# drivers.net
KiCad netlist of a schematic drawn in Altium Designer
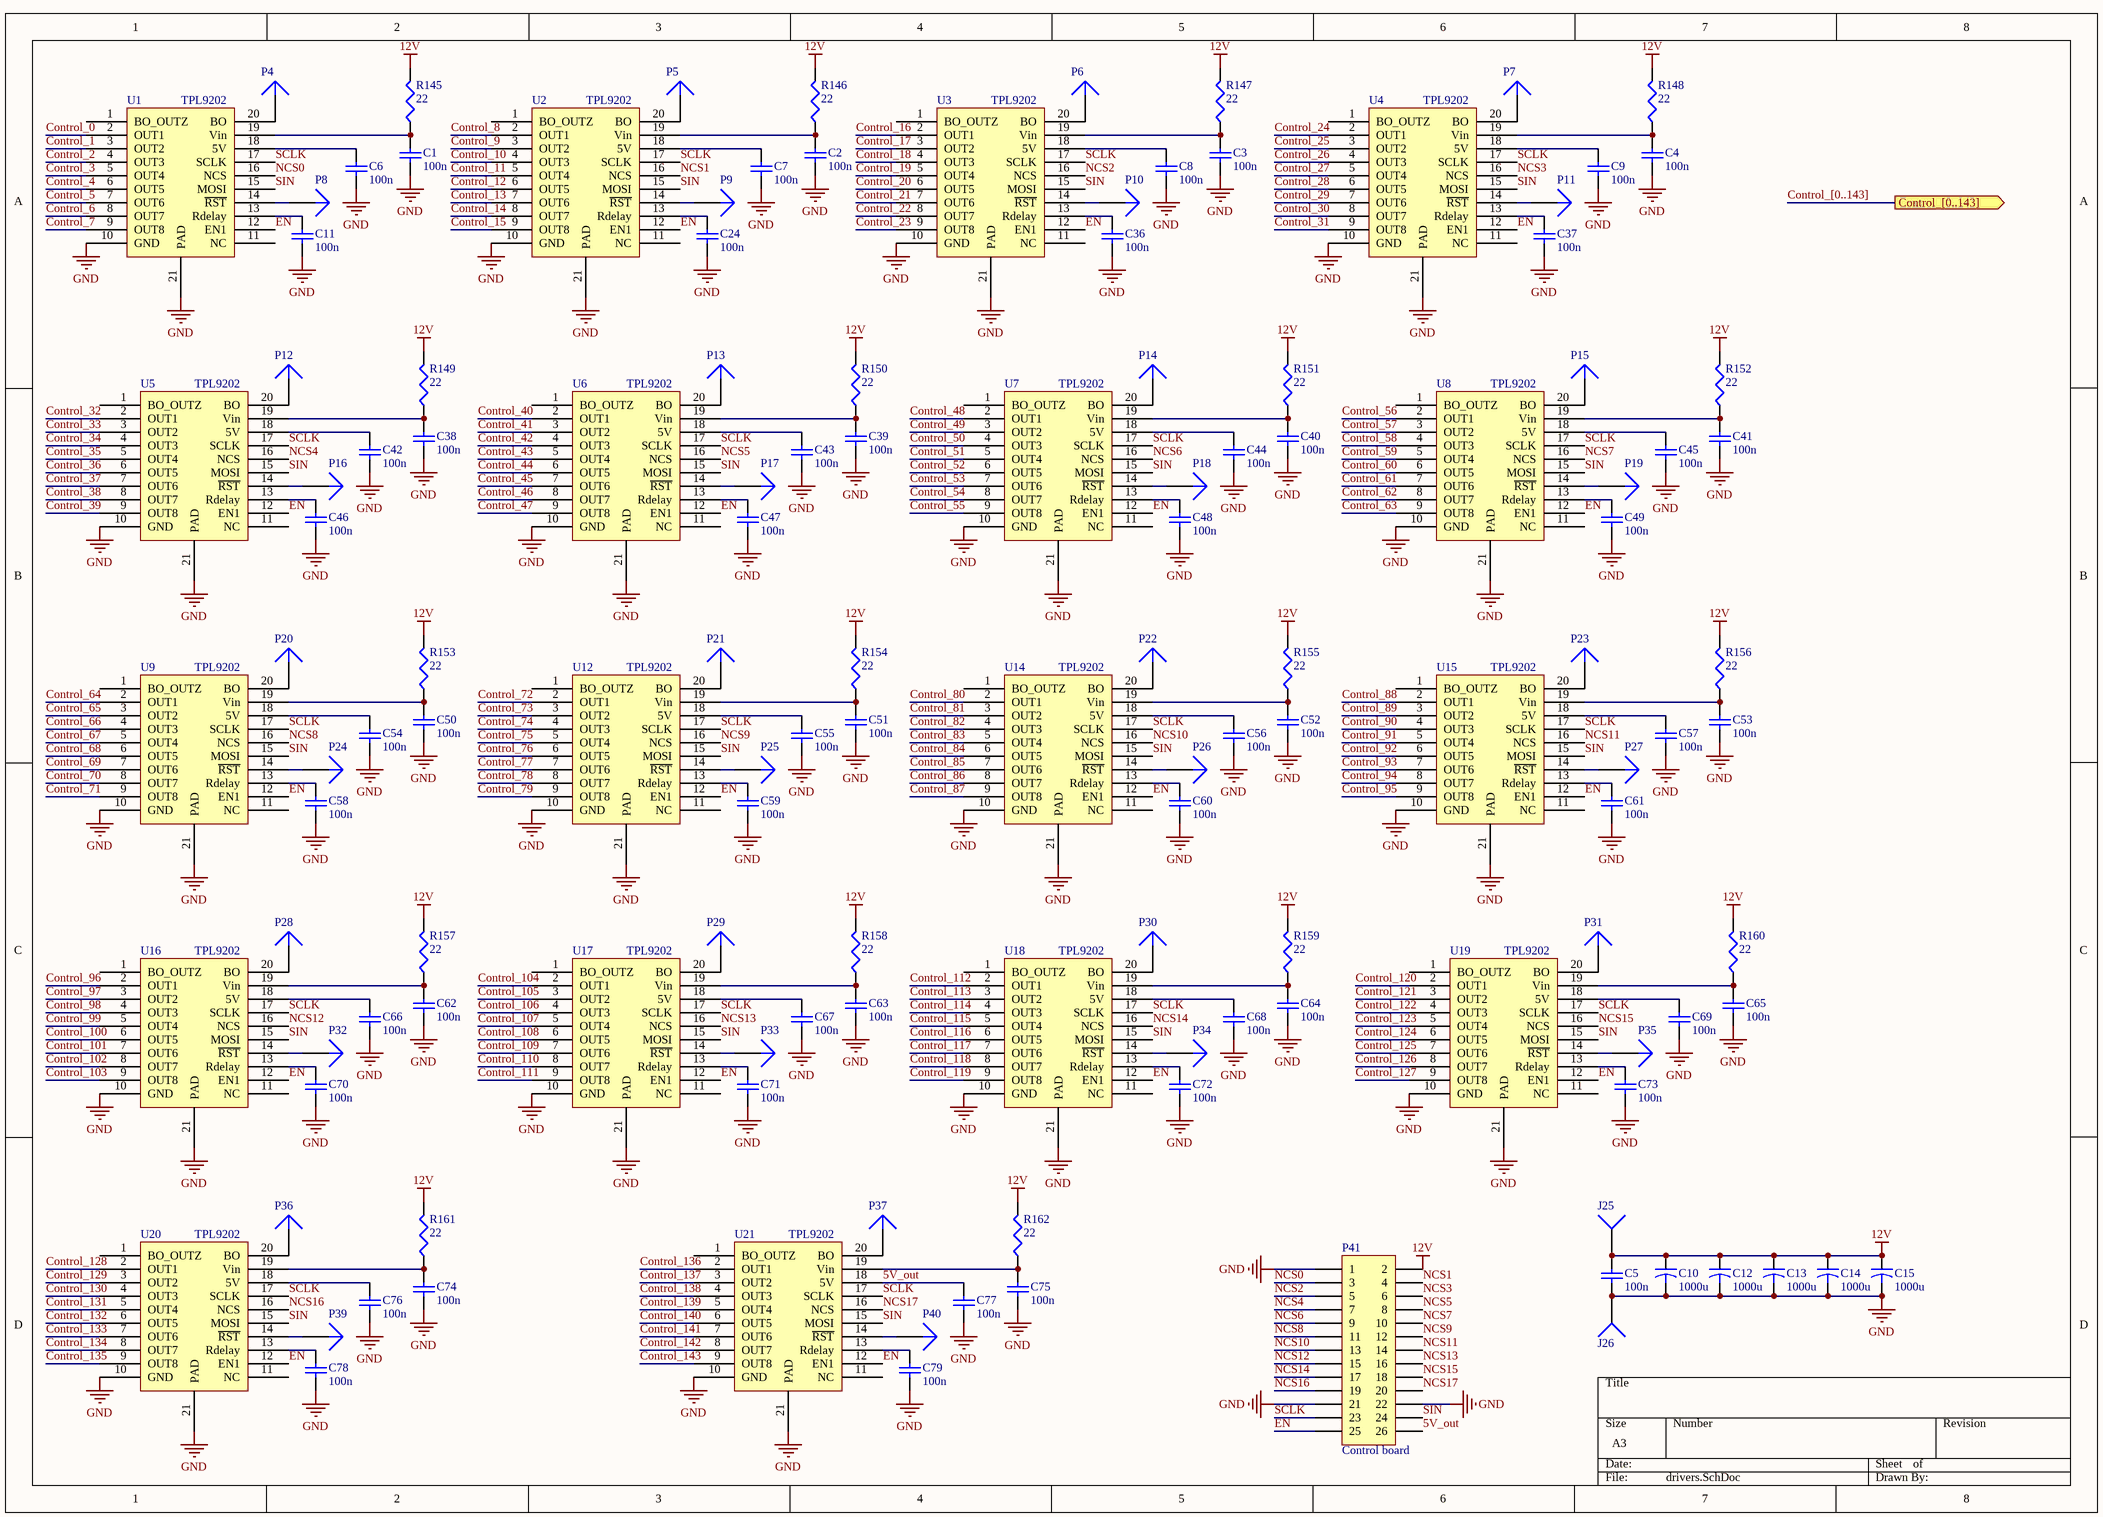
[diagram p0: drivers.SchDoc]

(export (version "E")
  (design (tool "Eeschema 10.0.6"))
  (components
    (comp (ref "C1")
      (value "100n")
      (footprint "1608[0603]")
      (description "Capacitor (Semiconductor SIM Model)")
      (fields (field (name "Comment") "Cap Semi") (field (name "PUBLISHER") "Altium Limited"))
      (libsource (lib "Miscellaneous Devices") (part "Cap Semi"))
    )
    (comp (ref "C2")
      (value "100n")
      (footprint "1608[0603]")
      (description "Capacitor (Semiconductor SIM Model)")
      (fields (field (name "Comment") "Cap Semi") (field (name "PUBLISHER") "Altium Limited"))
      (libsource (lib "Miscellaneous Devices") (part "Cap Semi"))
    )
    (comp (ref "C3")
      (value "100n")
      (footprint "1608[0603]")
      (description "Capacitor (Semiconductor SIM Model)")
      (fields (field (name "Comment") "Cap Semi") (field (name "PUBLISHER") "Altium Limited"))
      (libsource (lib "Miscellaneous Devices") (part "Cap Semi"))
    )
    (comp (ref "C4")
      (value "100n")
      (footprint "1608[0603]")
      (description "Capacitor (Semiconductor SIM Model)")
      (fields (field (name "Comment") "Cap Semi") (field (name "PUBLISHER") "Altium Limited"))
      (libsource (lib "Miscellaneous Devices") (part "Cap Semi"))
    )
    (comp (ref "C5")
      (value "100n")
      (footprint "1608[0603]")
      (description "Capacitor (Semiconductor SIM Model)")
      (fields (field (name "Comment") "Cap Semi") (field (name "PUBLISHER") "Altium Limited"))
      (libsource (lib "Miscellaneous Devices") (part "Cap Semi"))
    )
    (comp (ref "C6")
      (value "100n")
      (footprint "1608[0603]")
      (description "Capacitor (Semiconductor SIM Model)")
      (fields (field (name "Comment") "Cap Semi") (field (name "PUBLISHER") "Altium Limited"))
      (libsource (lib "Miscellaneous Devices") (part "Cap Semi"))
    )
    (comp (ref "C7")
      (value "100n")
      (footprint "1608[0603]")
      (description "Capacitor (Semiconductor SIM Model)")
      (fields (field (name "Comment") "Cap Semi") (field (name "PUBLISHER") "Altium Limited"))
      (libsource (lib "Miscellaneous Devices") (part "Cap Semi"))
    )
    (comp (ref "C8")
      (value "100n")
      (footprint "1608[0603]")
      (description "Capacitor (Semiconductor SIM Model)")
      (fields (field (name "Comment") "Cap Semi") (field (name "PUBLISHER") "Altium Limited"))
      (libsource (lib "Miscellaneous Devices") (part "Cap Semi"))
    )
    (comp (ref "C9")
      (value "100n")
      (footprint "1608[0603]")
      (description "Capacitor (Semiconductor SIM Model)")
      (fields (field (name "Comment") "Cap Semi") (field (name "PUBLISHER") "Altium Limited"))
      (libsource (lib "Miscellaneous Devices") (part "Cap Semi"))
    )
    (comp (ref "C10")
      (value "1000u")
      (footprint "Cap_10x16mm")
      (description "Capacitor")
      (fields (field (name "Comment") "Cap2") (field (name "PUBLISHER") "Altium Limited"))
      (libsource (lib "Miscellaneous Devices") (part "Cap2"))
    )
    (comp (ref "C11")
      (value "100n")
      (footprint "1608[0603]")
      (description "Capacitor (Semiconductor SIM Model)")
      (fields (field (name "Comment") "Cap Semi") (field (name "PUBLISHER") "Altium Limited"))
      (libsource (lib "Miscellaneous Devices") (part "Cap Semi"))
    )
    (comp (ref "C12")
      (value "1000u")
      (footprint "Cap_10x16mm")
      (description "Capacitor")
      (fields (field (name "Comment") "Cap2") (field (name "PUBLISHER") "Altium Limited"))
      (libsource (lib "Miscellaneous Devices") (part "Cap2"))
    )
    (comp (ref "C13")
      (value "1000u")
      (footprint "Cap_10x16mm")
      (description "Capacitor")
      (fields (field (name "Comment") "Cap2") (field (name "PUBLISHER") "Altium Limited"))
      (libsource (lib "Miscellaneous Devices") (part "Cap2"))
    )
    (comp (ref "C14")
      (value "1000u")
      (footprint "Cap_10x16mm")
      (description "Capacitor")
      (fields (field (name "Comment") "Cap2") (field (name "PUBLISHER") "Altium Limited"))
      (libsource (lib "Miscellaneous Devices") (part "Cap2"))
    )
    (comp (ref "C15")
      (value "1000u")
      (footprint "Cap_10x16mm")
      (description "Capacitor")
      (fields (field (name "Comment") "Cap2") (field (name "PUBLISHER") "Altium Limited"))
      (libsource (lib "Miscellaneous Devices") (part "Cap2"))
    )
    (comp (ref "C24")
      (value "100n")
      (footprint "1608[0603]")
      (description "Capacitor (Semiconductor SIM Model)")
      (fields (field (name "Comment") "Cap Semi") (field (name "PUBLISHER") "Altium Limited"))
      (libsource (lib "Miscellaneous Devices") (part "Cap Semi"))
    )
    (comp (ref "C36")
      (value "100n")
      (footprint "1608[0603]")
      (description "Capacitor (Semiconductor SIM Model)")
      (fields (field (name "Comment") "Cap Semi") (field (name "PUBLISHER") "Altium Limited"))
      (libsource (lib "Miscellaneous Devices") (part "Cap Semi"))
    )
    (comp (ref "C37")
      (value "100n")
      (footprint "1608[0603]")
      (description "Capacitor (Semiconductor SIM Model)")
      (fields (field (name "Comment") "Cap Semi") (field (name "PUBLISHER") "Altium Limited"))
      (libsource (lib "Miscellaneous Devices") (part "Cap Semi"))
    )
    (comp (ref "C38")
      (value "100n")
      (footprint "1608[0603]")
      (description "Capacitor (Semiconductor SIM Model)")
      (fields (field (name "Comment") "Cap Semi") (field (name "PUBLISHER") "Altium Limited"))
      (libsource (lib "Miscellaneous Devices") (part "Cap Semi"))
    )
    (comp (ref "C39")
      (value "100n")
      (footprint "1608[0603]")
      (description "Capacitor (Semiconductor SIM Model)")
      (fields (field (name "Comment") "Cap Semi") (field (name "PUBLISHER") "Altium Limited"))
      (libsource (lib "Miscellaneous Devices") (part "Cap Semi"))
    )
    (comp (ref "C40")
      (value "100n")
      (footprint "1608[0603]")
      (description "Capacitor (Semiconductor SIM Model)")
      (fields (field (name "Comment") "Cap Semi") (field (name "PUBLISHER") "Altium Limited"))
      (libsource (lib "Miscellaneous Devices") (part "Cap Semi"))
    )
    (comp (ref "C41")
      (value "100n")
      (footprint "1608[0603]")
      (description "Capacitor (Semiconductor SIM Model)")
      (fields (field (name "Comment") "Cap Semi") (field (name "PUBLISHER") "Altium Limited"))
      (libsource (lib "Miscellaneous Devices") (part "Cap Semi"))
    )
    (comp (ref "C42")
      (value "100n")
      (footprint "1608[0603]")
      (description "Capacitor (Semiconductor SIM Model)")
      (fields (field (name "Comment") "Cap Semi") (field (name "PUBLISHER") "Altium Limited"))
      (libsource (lib "Miscellaneous Devices") (part "Cap Semi"))
    )
    (comp (ref "C43")
      (value "100n")
      (footprint "1608[0603]")
      (description "Capacitor (Semiconductor SIM Model)")
      (fields (field (name "Comment") "Cap Semi") (field (name "PUBLISHER") "Altium Limited"))
      (libsource (lib "Miscellaneous Devices") (part "Cap Semi"))
    )
    (comp (ref "C44")
      (value "100n")
      (footprint "1608[0603]")
      (description "Capacitor (Semiconductor SIM Model)")
      (fields (field (name "Comment") "Cap Semi") (field (name "PUBLISHER") "Altium Limited"))
      (libsource (lib "Miscellaneous Devices") (part "Cap Semi"))
    )
    (comp (ref "C45")
      (value "100n")
      (footprint "1608[0603]")
      (description "Capacitor (Semiconductor SIM Model)")
      (fields (field (name "Comment") "Cap Semi") (field (name "PUBLISHER") "Altium Limited"))
      (libsource (lib "Miscellaneous Devices") (part "Cap Semi"))
    )
    (comp (ref "C46")
      (value "100n")
      (footprint "1608[0603]")
      (description "Capacitor (Semiconductor SIM Model)")
      (fields (field (name "Comment") "Cap Semi") (field (name "PUBLISHER") "Altium Limited"))
      (libsource (lib "Miscellaneous Devices") (part "Cap Semi"))
    )
    (comp (ref "C47")
      (value "100n")
      (footprint "1608[0603]")
      (description "Capacitor (Semiconductor SIM Model)")
      (fields (field (name "Comment") "Cap Semi") (field (name "PUBLISHER") "Altium Limited"))
      (libsource (lib "Miscellaneous Devices") (part "Cap Semi"))
    )
    (comp (ref "C48")
      (value "100n")
      (footprint "1608[0603]")
      (description "Capacitor (Semiconductor SIM Model)")
      (fields (field (name "Comment") "Cap Semi") (field (name "PUBLISHER") "Altium Limited"))
      (libsource (lib "Miscellaneous Devices") (part "Cap Semi"))
    )
    (comp (ref "C49")
      (value "100n")
      (footprint "1608[0603]")
      (description "Capacitor (Semiconductor SIM Model)")
      (fields (field (name "Comment") "Cap Semi") (field (name "PUBLISHER") "Altium Limited"))
      (libsource (lib "Miscellaneous Devices") (part "Cap Semi"))
    )
    (comp (ref "C50")
      (value "100n")
      (footprint "1608[0603]")
      (description "Capacitor (Semiconductor SIM Model)")
      (fields (field (name "Comment") "Cap Semi") (field (name "PUBLISHER") "Altium Limited"))
      (libsource (lib "Miscellaneous Devices") (part "Cap Semi"))
    )
    (comp (ref "C51")
      (value "100n")
      (footprint "1608[0603]")
      (description "Capacitor (Semiconductor SIM Model)")
      (fields (field (name "Comment") "Cap Semi") (field (name "PUBLISHER") "Altium Limited"))
      (libsource (lib "Miscellaneous Devices") (part "Cap Semi"))
    )
    (comp (ref "C52")
      (value "100n")
      (footprint "1608[0603]")
      (description "Capacitor (Semiconductor SIM Model)")
      (fields (field (name "Comment") "Cap Semi") (field (name "PUBLISHER") "Altium Limited"))
      (libsource (lib "Miscellaneous Devices") (part "Cap Semi"))
    )
    (comp (ref "C53")
      (value "100n")
      (footprint "1608[0603]")
      (description "Capacitor (Semiconductor SIM Model)")
      (fields (field (name "Comment") "Cap Semi") (field (name "PUBLISHER") "Altium Limited"))
      (libsource (lib "Miscellaneous Devices") (part "Cap Semi"))
    )
    (comp (ref "C54")
      (value "100n")
      (footprint "1608[0603]")
      (description "Capacitor (Semiconductor SIM Model)")
      (fields (field (name "Comment") "Cap Semi") (field (name "PUBLISHER") "Altium Limited"))
      (libsource (lib "Miscellaneous Devices") (part "Cap Semi"))
    )
    (comp (ref "C55")
      (value "100n")
      (footprint "1608[0603]")
      (description "Capacitor (Semiconductor SIM Model)")
      (fields (field (name "Comment") "Cap Semi") (field (name "PUBLISHER") "Altium Limited"))
      (libsource (lib "Miscellaneous Devices") (part "Cap Semi"))
    )
    (comp (ref "C56")
      (value "100n")
      (footprint "1608[0603]")
      (description "Capacitor (Semiconductor SIM Model)")
      (fields (field (name "Comment") "Cap Semi") (field (name "PUBLISHER") "Altium Limited"))
      (libsource (lib "Miscellaneous Devices") (part "Cap Semi"))
    )
    (comp (ref "C57")
      (value "100n")
      (footprint "1608[0603]")
      (description "Capacitor (Semiconductor SIM Model)")
      (fields (field (name "Comment") "Cap Semi") (field (name "PUBLISHER") "Altium Limited"))
      (libsource (lib "Miscellaneous Devices") (part "Cap Semi"))
    )
    (comp (ref "C58")
      (value "100n")
      (footprint "1608[0603]")
      (description "Capacitor (Semiconductor SIM Model)")
      (fields (field (name "Comment") "Cap Semi") (field (name "PUBLISHER") "Altium Limited"))
      (libsource (lib "Miscellaneous Devices") (part "Cap Semi"))
    )
    (comp (ref "C59")
      (value "100n")
      (footprint "1608[0603]")
      (description "Capacitor (Semiconductor SIM Model)")
      (fields (field (name "Comment") "Cap Semi") (field (name "PUBLISHER") "Altium Limited"))
      (libsource (lib "Miscellaneous Devices") (part "Cap Semi"))
    )
    (comp (ref "C60")
      (value "100n")
      (footprint "1608[0603]")
      (description "Capacitor (Semiconductor SIM Model)")
      (fields (field (name "Comment") "Cap Semi") (field (name "PUBLISHER") "Altium Limited"))
      (libsource (lib "Miscellaneous Devices") (part "Cap Semi"))
    )
    (comp (ref "C61")
      (value "100n")
      (footprint "1608[0603]")
      (description "Capacitor (Semiconductor SIM Model)")
      (fields (field (name "Comment") "Cap Semi") (field (name "PUBLISHER") "Altium Limited"))
      (libsource (lib "Miscellaneous Devices") (part "Cap Semi"))
    )
    (comp (ref "C62")
      (value "100n")
      (footprint "1608[0603]")
      (description "Capacitor (Semiconductor SIM Model)")
      (fields (field (name "Comment") "Cap Semi") (field (name "PUBLISHER") "Altium Limited"))
      (libsource (lib "Miscellaneous Devices") (part "Cap Semi"))
    )
    (comp (ref "C63")
      (value "100n")
      (footprint "1608[0603]")
      (description "Capacitor (Semiconductor SIM Model)")
      (fields (field (name "Comment") "Cap Semi") (field (name "PUBLISHER") "Altium Limited"))
      (libsource (lib "Miscellaneous Devices") (part "Cap Semi"))
    )
    (comp (ref "C64")
      (value "100n")
      (footprint "1608[0603]")
      (description "Capacitor (Semiconductor SIM Model)")
      (fields (field (name "Comment") "Cap Semi") (field (name "PUBLISHER") "Altium Limited"))
      (libsource (lib "Miscellaneous Devices") (part "Cap Semi"))
    )
    (comp (ref "C65")
      (value "100n")
      (footprint "1608[0603]")
      (description "Capacitor (Semiconductor SIM Model)")
      (fields (field (name "Comment") "Cap Semi") (field (name "PUBLISHER") "Altium Limited"))
      (libsource (lib "Miscellaneous Devices") (part "Cap Semi"))
    )
    (comp (ref "C66")
      (value "100n")
      (footprint "1608[0603]")
      (description "Capacitor (Semiconductor SIM Model)")
      (fields (field (name "Comment") "Cap Semi") (field (name "PUBLISHER") "Altium Limited"))
      (libsource (lib "Miscellaneous Devices") (part "Cap Semi"))
    )
    (comp (ref "C67")
      (value "100n")
      (footprint "1608[0603]")
      (description "Capacitor (Semiconductor SIM Model)")
      (fields (field (name "Comment") "Cap Semi") (field (name "PUBLISHER") "Altium Limited"))
      (libsource (lib "Miscellaneous Devices") (part "Cap Semi"))
    )
    (comp (ref "C68")
      (value "100n")
      (footprint "1608[0603]")
      (description "Capacitor (Semiconductor SIM Model)")
      (fields (field (name "Comment") "Cap Semi") (field (name "PUBLISHER") "Altium Limited"))
      (libsource (lib "Miscellaneous Devices") (part "Cap Semi"))
    )
    (comp (ref "C69")
      (value "100n")
      (footprint "1608[0603]")
      (description "Capacitor (Semiconductor SIM Model)")
      (fields (field (name "Comment") "Cap Semi") (field (name "PUBLISHER") "Altium Limited"))
      (libsource (lib "Miscellaneous Devices") (part "Cap Semi"))
    )
    (comp (ref "C70")
      (value "100n")
      (footprint "1608[0603]")
      (description "Capacitor (Semiconductor SIM Model)")
      (fields (field (name "Comment") "Cap Semi") (field (name "PUBLISHER") "Altium Limited"))
      (libsource (lib "Miscellaneous Devices") (part "Cap Semi"))
    )
    (comp (ref "C71")
      (value "100n")
      (footprint "1608[0603]")
      (description "Capacitor (Semiconductor SIM Model)")
      (fields (field (name "Comment") "Cap Semi") (field (name "PUBLISHER") "Altium Limited"))
      (libsource (lib "Miscellaneous Devices") (part "Cap Semi"))
    )
    (comp (ref "C72")
      (value "100n")
      (footprint "1608[0603]")
      (description "Capacitor (Semiconductor SIM Model)")
      (fields (field (name "Comment") "Cap Semi") (field (name "PUBLISHER") "Altium Limited"))
      (libsource (lib "Miscellaneous Devices") (part "Cap Semi"))
    )
    (comp (ref "C73")
      (value "100n")
      (footprint "1608[0603]")
      (description "Capacitor (Semiconductor SIM Model)")
      (fields (field (name "Comment") "Cap Semi") (field (name "PUBLISHER") "Altium Limited"))
      (libsource (lib "Miscellaneous Devices") (part "Cap Semi"))
    )
    (comp (ref "C74")
      (value "100n")
      (footprint "1608[0603]")
      (description "Capacitor (Semiconductor SIM Model)")
      (fields (field (name "Comment") "Cap Semi") (field (name "PUBLISHER") "Altium Limited"))
      (libsource (lib "Miscellaneous Devices") (part "Cap Semi"))
    )
    (comp (ref "C75")
      (value "100n")
      (footprint "1608[0603]")
      (description "Capacitor (Semiconductor SIM Model)")
      (fields (field (name "Comment") "Cap Semi") (field (name "PUBLISHER") "Altium Limited"))
      (libsource (lib "Miscellaneous Devices") (part "Cap Semi"))
    )
    (comp (ref "C76")
      (value "100n")
      (footprint "1608[0603]")
      (description "Capacitor (Semiconductor SIM Model)")
      (fields (field (name "Comment") "Cap Semi") (field (name "PUBLISHER") "Altium Limited"))
      (libsource (lib "Miscellaneous Devices") (part "Cap Semi"))
    )
    (comp (ref "C77")
      (value "100n")
      (footprint "1608[0603]")
      (description "Capacitor (Semiconductor SIM Model)")
      (fields (field (name "Comment") "Cap Semi") (field (name "PUBLISHER") "Altium Limited"))
      (libsource (lib "Miscellaneous Devices") (part "Cap Semi"))
    )
    (comp (ref "C78")
      (value "100n")
      (footprint "1608[0603]")
      (description "Capacitor (Semiconductor SIM Model)")
      (fields (field (name "Comment") "Cap Semi") (field (name "PUBLISHER") "Altium Limited"))
      (libsource (lib "Miscellaneous Devices") (part "Cap Semi"))
    )
    (comp (ref "C79")
      (value "100n")
      (footprint "1608[0603]")
      (description "Capacitor (Semiconductor SIM Model)")
      (fields (field (name "Comment") "Cap Semi") (field (name "PUBLISHER") "Altium Limited"))
      (libsource (lib "Miscellaneous Devices") (part "Cap Semi"))
    )
    (comp (ref "J25")
      (value "Audio")
      (footprint "Conn_1_2x4")
      (description "Socket")
      (fields (field (name "PUBLISHER") "Altium Limited"))
      (libsource (lib "Miscellaneous Connectors") (part "Socket"))
    )
    (comp (ref "J26")
      (value "Audio")
      (footprint "Conn_1_2x4")
      (description "Socket")
      (fields (field (name "PUBLISHER") "Altium Limited"))
      (libsource (lib "Miscellaneous Connectors") (part "Socket"))
    )
    (comp (ref "P4")
      (value "Plug")
      (footprint "PIN1")
      (fields (field (name "PUBLISHER") "Altium Limited"))
      (libsource (lib "Miscellaneous Connectors") (part "Plug"))
    )
    (comp (ref "P5")
      (value "Plug")
      (footprint "PIN1")
      (fields (field (name "PUBLISHER") "Altium Limited"))
      (libsource (lib "Miscellaneous Connectors") (part "Plug"))
    )
    (comp (ref "P6")
      (value "Plug")
      (footprint "PIN1")
      (fields (field (name "PUBLISHER") "Altium Limited"))
      (libsource (lib "Miscellaneous Connectors") (part "Plug"))
    )
    (comp (ref "P7")
      (value "Plug")
      (footprint "PIN1")
      (fields (field (name "PUBLISHER") "Altium Limited"))
      (libsource (lib "Miscellaneous Connectors") (part "Plug"))
    )
    (comp (ref "P8")
      (value "Plug")
      (footprint "PIN1")
      (fields (field (name "PUBLISHER") "Altium Limited"))
      (libsource (lib "Miscellaneous Connectors") (part "Plug"))
    )
    (comp (ref "P9")
      (value "Plug")
      (footprint "PIN1")
      (fields (field (name "PUBLISHER") "Altium Limited"))
      (libsource (lib "Miscellaneous Connectors") (part "Plug"))
    )
    (comp (ref "P10")
      (value "Plug")
      (footprint "PIN1")
      (fields (field (name "PUBLISHER") "Altium Limited"))
      (libsource (lib "Miscellaneous Connectors") (part "Plug"))
    )
    (comp (ref "P11")
      (value "Plug")
      (footprint "PIN1")
      (fields (field (name "PUBLISHER") "Altium Limited"))
      (libsource (lib "Miscellaneous Connectors") (part "Plug"))
    )
    (comp (ref "P12")
      (value "Plug")
      (footprint "PIN1")
      (fields (field (name "PUBLISHER") "Altium Limited"))
      (libsource (lib "Miscellaneous Connectors") (part "Plug"))
    )
    (comp (ref "P13")
      (value "Plug")
      (footprint "PIN1")
      (fields (field (name "PUBLISHER") "Altium Limited"))
      (libsource (lib "Miscellaneous Connectors") (part "Plug"))
    )
    (comp (ref "P14")
      (value "Plug")
      (footprint "PIN1")
      (fields (field (name "PUBLISHER") "Altium Limited"))
      (libsource (lib "Miscellaneous Connectors") (part "Plug"))
    )
    (comp (ref "P15")
      (value "Plug")
      (footprint "PIN1")
      (fields (field (name "PUBLISHER") "Altium Limited"))
      (libsource (lib "Miscellaneous Connectors") (part "Plug"))
    )
    (comp (ref "P16")
      (value "Plug")
      (footprint "PIN1")
      (fields (field (name "PUBLISHER") "Altium Limited"))
      (libsource (lib "Miscellaneous Connectors") (part "Plug"))
    )
    (comp (ref "P17")
      (value "Plug")
      (footprint "PIN1")
      (fields (field (name "PUBLISHER") "Altium Limited"))
      (libsource (lib "Miscellaneous Connectors") (part "Plug"))
    )
    (comp (ref "P18")
      (value "Plug")
      (footprint "PIN1")
      (fields (field (name "PUBLISHER") "Altium Limited"))
      (libsource (lib "Miscellaneous Connectors") (part "Plug"))
    )
    (comp (ref "P19")
      (value "Plug")
      (footprint "PIN1")
      (fields (field (name "PUBLISHER") "Altium Limited"))
      (libsource (lib "Miscellaneous Connectors") (part "Plug"))
    )
    (comp (ref "P20")
      (value "Plug")
      (footprint "PIN1")
      (fields (field (name "PUBLISHER") "Altium Limited"))
      (libsource (lib "Miscellaneous Connectors") (part "Plug"))
    )
    (comp (ref "P21")
      (value "Plug")
      (footprint "PIN1")
      (fields (field (name "PUBLISHER") "Altium Limited"))
      (libsource (lib "Miscellaneous Connectors") (part "Plug"))
    )
    (comp (ref "P22")
      (value "Plug")
      (footprint "PIN1")
      (fields (field (name "PUBLISHER") "Altium Limited"))
      (libsource (lib "Miscellaneous Connectors") (part "Plug"))
    )
    (comp (ref "P23")
      (value "Plug")
      (footprint "PIN1")
      (fields (field (name "PUBLISHER") "Altium Limited"))
      (libsource (lib "Miscellaneous Connectors") (part "Plug"))
    )
    (comp (ref "P24")
      (value "Plug")
      (footprint "PIN1")
      (fields (field (name "PUBLISHER") "Altium Limited"))
      (libsource (lib "Miscellaneous Connectors") (part "Plug"))
    )
    (comp (ref "P25")
      (value "Plug")
      (footprint "PIN1")
      (fields (field (name "PUBLISHER") "Altium Limited"))
      (libsource (lib "Miscellaneous Connectors") (part "Plug"))
    )
    (comp (ref "P26")
      (value "Plug")
      (footprint "PIN1")
      (fields (field (name "PUBLISHER") "Altium Limited"))
      (libsource (lib "Miscellaneous Connectors") (part "Plug"))
    )
    (comp (ref "P27")
      (value "Plug")
      (footprint "PIN1")
      (fields (field (name "PUBLISHER") "Altium Limited"))
      (libsource (lib "Miscellaneous Connectors") (part "Plug"))
    )
    (comp (ref "P28")
      (value "Plug")
      (footprint "PIN1")
      (fields (field (name "PUBLISHER") "Altium Limited"))
      (libsource (lib "Miscellaneous Connectors") (part "Plug"))
    )
    (comp (ref "P29")
      (value "Plug")
      (footprint "PIN1")
      (fields (field (name "PUBLISHER") "Altium Limited"))
      (libsource (lib "Miscellaneous Connectors") (part "Plug"))
    )
    (comp (ref "P30")
      (value "Plug")
      (footprint "PIN1")
      (fields (field (name "PUBLISHER") "Altium Limited"))
      (libsource (lib "Miscellaneous Connectors") (part "Plug"))
    )
    (comp (ref "P31")
      (value "Plug")
      (footprint "PIN1")
      (fields (field (name "PUBLISHER") "Altium Limited"))
      (libsource (lib "Miscellaneous Connectors") (part "Plug"))
    )
    (comp (ref "P32")
      (value "Plug")
      (footprint "PIN1")
      (fields (field (name "PUBLISHER") "Altium Limited"))
      (libsource (lib "Miscellaneous Connectors") (part "Plug"))
    )
    (comp (ref "P33")
      (value "Plug")
      (footprint "PIN1")
      (fields (field (name "PUBLISHER") "Altium Limited"))
      (libsource (lib "Miscellaneous Connectors") (part "Plug"))
    )
    (comp (ref "P34")
      (value "Plug")
      (footprint "PIN1")
      (fields (field (name "PUBLISHER") "Altium Limited"))
      (libsource (lib "Miscellaneous Connectors") (part "Plug"))
    )
    (comp (ref "P35")
      (value "Plug")
      (footprint "PIN1")
      (fields (field (name "PUBLISHER") "Altium Limited"))
      (libsource (lib "Miscellaneous Connectors") (part "Plug"))
    )
    (comp (ref "P36")
      (value "Plug")
      (footprint "PIN1")
      (fields (field (name "PUBLISHER") "Altium Limited"))
      (libsource (lib "Miscellaneous Connectors") (part "Plug"))
    )
    (comp (ref "P37")
      (value "Plug")
      (footprint "PIN1")
      (fields (field (name "PUBLISHER") "Altium Limited"))
      (libsource (lib "Miscellaneous Connectors") (part "Plug"))
    )
    (comp (ref "P39")
      (value "Plug")
      (footprint "PIN1")
      (fields (field (name "PUBLISHER") "Altium Limited"))
      (libsource (lib "Miscellaneous Connectors") (part "Plug"))
    )
    (comp (ref "P40")
      (value "Plug")
      (footprint "PIN1")
      (fields (field (name "PUBLISHER") "Altium Limited"))
      (libsource (lib "Miscellaneous Connectors") (part "Plug"))
    )
    (comp (ref "P41")
      (value "Control board")
      (footprint "HDR2X13")
      (description "Header, 13-Pin, Dual row")
      (fields (field (name "PUBLISHER") "Altium Limited"))
      (libsource (lib "Miscellaneous Connectors") (part "Header 13X2"))
    )
    (comp (ref "R145")
      (value "22")
      (footprint "C2512")
      (description "Resistor")
      (fields (field (name "Comment") "Res3") (field (name "PUBLISHER") "Altium Limited"))
      (libsource (lib "Miscellaneous Devices") (part "Res3"))
    )
    (comp (ref "R146")
      (value "22")
      (footprint "C2512")
      (description "Resistor")
      (fields (field (name "Comment") "Res3") (field (name "PUBLISHER") "Altium Limited"))
      (libsource (lib "Miscellaneous Devices") (part "Res3"))
    )
    (comp (ref "R147")
      (value "22")
      (footprint "C2512")
      (description "Resistor")
      (fields (field (name "Comment") "Res3") (field (name "PUBLISHER") "Altium Limited"))
      (libsource (lib "Miscellaneous Devices") (part "Res3"))
    )
    (comp (ref "R148")
      (value "22")
      (footprint "C2512")
      (description "Resistor")
      (fields (field (name "Comment") "Res3") (field (name "PUBLISHER") "Altium Limited"))
      (libsource (lib "Miscellaneous Devices") (part "Res3"))
    )
    (comp (ref "R149")
      (value "22")
      (footprint "C2512")
      (description "Resistor")
      (fields (field (name "Comment") "Res3") (field (name "PUBLISHER") "Altium Limited"))
      (libsource (lib "Miscellaneous Devices") (part "Res3"))
    )
    (comp (ref "R150")
      (value "22")
      (footprint "C2512")
      (description "Resistor")
      (fields (field (name "Comment") "Res3") (field (name "PUBLISHER") "Altium Limited"))
      (libsource (lib "Miscellaneous Devices") (part "Res3"))
    )
    (comp (ref "R151")
      (value "22")
      (footprint "C2512")
      (description "Resistor")
      (fields (field (name "Comment") "Res3") (field (name "PUBLISHER") "Altium Limited"))
      (libsource (lib "Miscellaneous Devices") (part "Res3"))
    )
    (comp (ref "R152")
      (value "22")
      (footprint "C2512")
      (description "Resistor")
      (fields (field (name "Comment") "Res3") (field (name "PUBLISHER") "Altium Limited"))
      (libsource (lib "Miscellaneous Devices") (part "Res3"))
    )
    (comp (ref "R153")
      (value "22")
      (footprint "C2512")
      (description "Resistor")
      (fields (field (name "Comment") "Res3") (field (name "PUBLISHER") "Altium Limited"))
      (libsource (lib "Miscellaneous Devices") (part "Res3"))
    )
    (comp (ref "R154")
      (value "22")
      (footprint "C2512")
      (description "Resistor")
      (fields (field (name "Comment") "Res3") (field (name "PUBLISHER") "Altium Limited"))
      (libsource (lib "Miscellaneous Devices") (part "Res3"))
    )
    (comp (ref "R155")
      (value "22")
      (footprint "C2512")
      (description "Resistor")
      (fields (field (name "Comment") "Res3") (field (name "PUBLISHER") "Altium Limited"))
      (libsource (lib "Miscellaneous Devices") (part "Res3"))
    )
    (comp (ref "R156")
      (value "22")
      (footprint "C2512")
      (description "Resistor")
      (fields (field (name "Comment") "Res3") (field (name "PUBLISHER") "Altium Limited"))
      (libsource (lib "Miscellaneous Devices") (part "Res3"))
    )
    (comp (ref "R157")
      (value "22")
      (footprint "C2512")
      (description "Resistor")
      (fields (field (name "Comment") "Res3") (field (name "PUBLISHER") "Altium Limited"))
      (libsource (lib "Miscellaneous Devices") (part "Res3"))
    )
    (comp (ref "R158")
      (value "22")
      (footprint "C2512")
      (description "Resistor")
      (fields (field (name "Comment") "Res3") (field (name "PUBLISHER") "Altium Limited"))
      (libsource (lib "Miscellaneous Devices") (part "Res3"))
    )
    (comp (ref "R159")
      (value "22")
      (footprint "C2512")
      (description "Resistor")
      (fields (field (name "Comment") "Res3") (field (name "PUBLISHER") "Altium Limited"))
      (libsource (lib "Miscellaneous Devices") (part "Res3"))
    )
    (comp (ref "R160")
      (value "22")
      (footprint "C2512")
      (description "Resistor")
      (fields (field (name "Comment") "Res3") (field (name "PUBLISHER") "Altium Limited"))
      (libsource (lib "Miscellaneous Devices") (part "Res3"))
    )
    (comp (ref "R161")
      (value "22")
      (footprint "C2512")
      (description "Resistor")
      (fields (field (name "Comment") "Res3") (field (name "PUBLISHER") "Altium Limited"))
      (libsource (lib "Miscellaneous Devices") (part "Res3"))
    )
    (comp (ref "R162")
      (value "22")
      (footprint "C2512")
      (description "Resistor")
      (fields (field (name "Comment") "Res3") (field (name "PUBLISHER") "Altium Limited"))
      (libsource (lib "Miscellaneous Devices") (part "Res3"))
    )
    (comp (ref "U1")
      (value "TPL9202")
      (footprint "HSSOP20")
      (description "8-CHANNEL RELAY DRIVER  WITH INTEGRATED 5-V LDO AND BROWN-OUT DETECTION")
      (fields (field (name "PART NUMBER") "809-5425"))
      (libsource (lib "tech-thing") (part "TPL9202"))
    )
    (comp (ref "U2")
      (value "TPL9202")
      (footprint "HSSOP20")
      (description "8-CHANNEL RELAY DRIVER  WITH INTEGRATED 5-V LDO AND BROWN-OUT DETECTION")
      (fields (field (name "PART NUMBER") "809-5425"))
      (libsource (lib "tech-thing") (part "TPL9202"))
    )
    (comp (ref "U3")
      (value "TPL9202")
      (footprint "HSSOP20")
      (description "8-CHANNEL RELAY DRIVER  WITH INTEGRATED 5-V LDO AND BROWN-OUT DETECTION")
      (fields (field (name "PART NUMBER") "809-5425"))
      (libsource (lib "tech-thing") (part "TPL9202"))
    )
    (comp (ref "U4")
      (value "TPL9202")
      (footprint "HSSOP20")
      (description "8-CHANNEL RELAY DRIVER  WITH INTEGRATED 5-V LDO AND BROWN-OUT DETECTION")
      (fields (field (name "PART NUMBER") "809-5425"))
      (libsource (lib "tech-thing") (part "TPL9202"))
    )
    (comp (ref "U5")
      (value "TPL9202")
      (footprint "HSSOP20")
      (description "8-CHANNEL RELAY DRIVER  WITH INTEGRATED 5-V LDO AND BROWN-OUT DETECTION")
      (fields (field (name "PART NUMBER") "809-5425"))
      (libsource (lib "tech-thing") (part "TPL9202"))
    )
    (comp (ref "U6")
      (value "TPL9202")
      (footprint "HSSOP20")
      (description "8-CHANNEL RELAY DRIVER  WITH INTEGRATED 5-V LDO AND BROWN-OUT DETECTION")
      (fields (field (name "PART NUMBER") "809-5425"))
      (libsource (lib "tech-thing") (part "TPL9202"))
    )
    (comp (ref "U7")
      (value "TPL9202")
      (footprint "HSSOP20")
      (description "8-CHANNEL RELAY DRIVER  WITH INTEGRATED 5-V LDO AND BROWN-OUT DETECTION")
      (fields (field (name "PART NUMBER") "809-5425"))
      (libsource (lib "tech-thing") (part "TPL9202"))
    )
    (comp (ref "U8")
      (value "TPL9202")
      (footprint "HSSOP20")
      (description "8-CHANNEL RELAY DRIVER  WITH INTEGRATED 5-V LDO AND BROWN-OUT DETECTION")
      (fields (field (name "PART NUMBER") "809-5425"))
      (libsource (lib "tech-thing") (part "TPL9202"))
    )
    (comp (ref "U9")
      (value "TPL9202")
      (footprint "HSSOP20")
      (description "8-CHANNEL RELAY DRIVER  WITH INTEGRATED 5-V LDO AND BROWN-OUT DETECTION")
      (fields (field (name "PART NUMBER") "809-5425"))
      (libsource (lib "tech-thing") (part "TPL9202"))
    )
    (comp (ref "U12")
      (value "TPL9202")
      (footprint "HSSOP20")
      (description "8-CHANNEL RELAY DRIVER  WITH INTEGRATED 5-V LDO AND BROWN-OUT DETECTION")
      (fields (field (name "PART NUMBER") "809-5425"))
      (libsource (lib "tech-thing") (part "TPL9202"))
    )
    (comp (ref "U14")
      (value "TPL9202")
      (footprint "HSSOP20")
      (description "8-CHANNEL RELAY DRIVER  WITH INTEGRATED 5-V LDO AND BROWN-OUT DETECTION")
      (fields (field (name "PART NUMBER") "809-5425"))
      (libsource (lib "tech-thing") (part "TPL9202"))
    )
    (comp (ref "U15")
      (value "TPL9202")
      (footprint "HSSOP20")
      (description "8-CHANNEL RELAY DRIVER  WITH INTEGRATED 5-V LDO AND BROWN-OUT DETECTION")
      (fields (field (name "PART NUMBER") "809-5425"))
      (libsource (lib "tech-thing") (part "TPL9202"))
    )
    (comp (ref "U16")
      (value "TPL9202")
      (footprint "HSSOP20")
      (description "8-CHANNEL RELAY DRIVER  WITH INTEGRATED 5-V LDO AND BROWN-OUT DETECTION")
      (fields (field (name "PART NUMBER") "809-5425"))
      (libsource (lib "tech-thing") (part "TPL9202"))
    )
    (comp (ref "U17")
      (value "TPL9202")
      (footprint "HSSOP20")
      (description "8-CHANNEL RELAY DRIVER  WITH INTEGRATED 5-V LDO AND BROWN-OUT DETECTION")
      (fields (field (name "PART NUMBER") "809-5425"))
      (libsource (lib "tech-thing") (part "TPL9202"))
    )
    (comp (ref "U18")
      (value "TPL9202")
      (footprint "HSSOP20")
      (description "8-CHANNEL RELAY DRIVER  WITH INTEGRATED 5-V LDO AND BROWN-OUT DETECTION")
      (fields (field (name "PART NUMBER") "809-5425"))
      (libsource (lib "tech-thing") (part "TPL9202"))
    )
    (comp (ref "U19")
      (value "TPL9202")
      (footprint "HSSOP20")
      (description "8-CHANNEL RELAY DRIVER  WITH INTEGRATED 5-V LDO AND BROWN-OUT DETECTION")
      (fields (field (name "PART NUMBER") "809-5425"))
      (libsource (lib "tech-thing") (part "TPL9202"))
    )
    (comp (ref "U20")
      (value "TPL9202")
      (footprint "HSSOP20")
      (description "8-CHANNEL RELAY DRIVER  WITH INTEGRATED 5-V LDO AND BROWN-OUT DETECTION")
      (fields (field (name "PART NUMBER") "809-5425"))
      (libsource (lib "tech-thing") (part "TPL9202"))
    )
    (comp (ref "U21")
      (value "TPL9202")
      (footprint "HSSOP20")
      (description "8-CHANNEL RELAY DRIVER  WITH INTEGRATED 5-V LDO AND BROWN-OUT DETECTION")
      (fields (field (name "PART NUMBER") "809-5425"))
      (libsource (lib "tech-thing") (part "TPL9202"))
    )
  )
  (nets
    (net (code "1") (name "/5V_out") (class "Default")
      (node (ref "C77") (pin "2") (pinfunction "2_2") (pintype "passive"))
      (node (ref "P41") (pin "26") (pinfunction "26_26") (pintype "passive"))
      (node (ref "U21") (pin "18") (pinfunction "5V_18") (pintype "passive"))
    )
    (net (code "2") (name "/Control_0") (class "Default")
      (node (ref "U1") (pin "2") (pinfunction "OUT1_2") (pintype "passive"))
    )
    (net (code "3") (name "/Control_1") (class "Default")
      (node (ref "U1") (pin "3") (pinfunction "OUT2_3") (pintype "passive"))
    )
    (net (code "4") (name "/Control_2") (class "Default")
      (node (ref "U1") (pin "4") (pinfunction "OUT3_4") (pintype "passive"))
    )
    (net (code "5") (name "/Control_3") (class "Default")
      (node (ref "U1") (pin "5") (pinfunction "OUT4_5") (pintype "passive"))
    )
    (net (code "6") (name "/Control_4") (class "Default")
      (node (ref "U1") (pin "6") (pinfunction "OUT5_6") (pintype "passive"))
    )
    (net (code "7") (name "/Control_5") (class "Default")
      (node (ref "U1") (pin "7") (pinfunction "OUT6_7") (pintype "passive"))
    )
    (net (code "8") (name "/Control_6") (class "Default")
      (node (ref "U1") (pin "8") (pinfunction "OUT7_8") (pintype "passive"))
    )
    (net (code "9") (name "/Control_7") (class "Default")
      (node (ref "U1") (pin "9") (pinfunction "OUT8_9") (pintype "passive"))
    )
    (net (code "10") (name "/Control_8") (class "Default")
      (node (ref "U2") (pin "2") (pinfunction "OUT1_2") (pintype "passive"))
    )
    (net (code "11") (name "/Control_9") (class "Default")
      (node (ref "U2") (pin "3") (pinfunction "OUT2_3") (pintype "passive"))
    )
    (net (code "12") (name "/Control_10") (class "Default")
      (node (ref "U2") (pin "4") (pinfunction "OUT3_4") (pintype "passive"))
    )
    (net (code "13") (name "/Control_11") (class "Default")
      (node (ref "U2") (pin "5") (pinfunction "OUT4_5") (pintype "passive"))
    )
    (net (code "14") (name "/Control_12") (class "Default")
      (node (ref "U2") (pin "6") (pinfunction "OUT5_6") (pintype "passive"))
    )
    (net (code "15") (name "/Control_13") (class "Default")
      (node (ref "U2") (pin "7") (pinfunction "OUT6_7") (pintype "passive"))
    )
    (net (code "16") (name "/Control_14") (class "Default")
      (node (ref "U2") (pin "8") (pinfunction "OUT7_8") (pintype "passive"))
    )
    (net (code "17") (name "/Control_15") (class "Default")
      (node (ref "U2") (pin "9") (pinfunction "OUT8_9") (pintype "passive"))
    )
    (net (code "18") (name "/Control_16") (class "Default")
      (node (ref "U3") (pin "2") (pinfunction "OUT1_2") (pintype "passive"))
    )
    (net (code "19") (name "/Control_17") (class "Default")
      (node (ref "U3") (pin "3") (pinfunction "OUT2_3") (pintype "passive"))
    )
    (net (code "20") (name "/Control_18") (class "Default")
      (node (ref "U3") (pin "4") (pinfunction "OUT3_4") (pintype "passive"))
    )
    (net (code "21") (name "/Control_19") (class "Default")
      (node (ref "U3") (pin "5") (pinfunction "OUT4_5") (pintype "passive"))
    )
    (net (code "22") (name "/Control_20") (class "Default")
      (node (ref "U3") (pin "6") (pinfunction "OUT5_6") (pintype "passive"))
    )
    (net (code "23") (name "/Control_21") (class "Default")
      (node (ref "U3") (pin "7") (pinfunction "OUT6_7") (pintype "passive"))
    )
    (net (code "24") (name "/Control_22") (class "Default")
      (node (ref "U3") (pin "8") (pinfunction "OUT7_8") (pintype "passive"))
    )
    (net (code "25") (name "/Control_23") (class "Default")
      (node (ref "U3") (pin "9") (pinfunction "OUT8_9") (pintype "passive"))
    )
    (net (code "26") (name "/Control_24") (class "Default")
      (node (ref "U4") (pin "2") (pinfunction "OUT1_2") (pintype "passive"))
    )
    (net (code "27") (name "/Control_25") (class "Default")
      (node (ref "U4") (pin "3") (pinfunction "OUT2_3") (pintype "passive"))
    )
    (net (code "28") (name "/Control_26") (class "Default")
      (node (ref "U4") (pin "4") (pinfunction "OUT3_4") (pintype "passive"))
    )
    (net (code "29") (name "/Control_27") (class "Default")
      (node (ref "U4") (pin "5") (pinfunction "OUT4_5") (pintype "passive"))
    )
    (net (code "30") (name "/Control_28") (class "Default")
      (node (ref "U4") (pin "6") (pinfunction "OUT5_6") (pintype "passive"))
    )
    (net (code "31") (name "/Control_29") (class "Default")
      (node (ref "U4") (pin "7") (pinfunction "OUT6_7") (pintype "passive"))
    )
    (net (code "32") (name "/Control_30") (class "Default")
      (node (ref "U4") (pin "8") (pinfunction "OUT7_8") (pintype "passive"))
    )
    (net (code "33") (name "/Control_31") (class "Default")
      (node (ref "U4") (pin "9") (pinfunction "OUT8_9") (pintype "passive"))
    )
    (net (code "34") (name "/Control_32") (class "Default")
      (node (ref "U5") (pin "2") (pinfunction "OUT1_2") (pintype "passive"))
    )
    (net (code "35") (name "/Control_33") (class "Default")
      (node (ref "U5") (pin "3") (pinfunction "OUT2_3") (pintype "passive"))
    )
    (net (code "36") (name "/Control_34") (class "Default")
      (node (ref "U5") (pin "4") (pinfunction "OUT3_4") (pintype "passive"))
    )
    (net (code "37") (name "/Control_35") (class "Default")
      (node (ref "U5") (pin "5") (pinfunction "OUT4_5") (pintype "passive"))
    )
    (net (code "38") (name "/Control_36") (class "Default")
      (node (ref "U5") (pin "6") (pinfunction "OUT5_6") (pintype "passive"))
    )
    (net (code "39") (name "/Control_37") (class "Default")
      (node (ref "U5") (pin "7") (pinfunction "OUT6_7") (pintype "passive"))
    )
    (net (code "40") (name "/Control_38") (class "Default")
      (node (ref "U5") (pin "8") (pinfunction "OUT7_8") (pintype "passive"))
    )
    (net (code "41") (name "/Control_39") (class "Default")
      (node (ref "U5") (pin "9") (pinfunction "OUT8_9") (pintype "passive"))
    )
    (net (code "42") (name "/Control_40") (class "Default")
      (node (ref "U6") (pin "2") (pinfunction "OUT1_2") (pintype "passive"))
    )
    (net (code "43") (name "/Control_41") (class "Default")
      (node (ref "U6") (pin "3") (pinfunction "OUT2_3") (pintype "passive"))
    )
    (net (code "44") (name "/Control_42") (class "Default")
      (node (ref "U6") (pin "4") (pinfunction "OUT3_4") (pintype "passive"))
    )
    (net (code "45") (name "/Control_43") (class "Default")
      (node (ref "U6") (pin "5") (pinfunction "OUT4_5") (pintype "passive"))
    )
    (net (code "46") (name "/Control_44") (class "Default")
      (node (ref "U6") (pin "6") (pinfunction "OUT5_6") (pintype "passive"))
    )
    (net (code "47") (name "/Control_45") (class "Default")
      (node (ref "U6") (pin "7") (pinfunction "OUT6_7") (pintype "passive"))
    )
    (net (code "48") (name "/Control_46") (class "Default")
      (node (ref "U6") (pin "8") (pinfunction "OUT7_8") (pintype "passive"))
    )
    (net (code "49") (name "/Control_47") (class "Default")
      (node (ref "U6") (pin "9") (pinfunction "OUT8_9") (pintype "passive"))
    )
    (net (code "50") (name "/Control_48") (class "Default")
      (node (ref "U7") (pin "2") (pinfunction "OUT1_2") (pintype "passive"))
    )
    (net (code "51") (name "/Control_49") (class "Default")
      (node (ref "U7") (pin "3") (pinfunction "OUT2_3") (pintype "passive"))
    )
    (net (code "52") (name "/Control_50") (class "Default")
      (node (ref "U7") (pin "4") (pinfunction "OUT3_4") (pintype "passive"))
    )
    (net (code "53") (name "/Control_51") (class "Default")
      (node (ref "U7") (pin "5") (pinfunction "OUT4_5") (pintype "passive"))
    )
    (net (code "54") (name "/Control_52") (class "Default")
      (node (ref "U7") (pin "6") (pinfunction "OUT5_6") (pintype "passive"))
    )
    (net (code "55") (name "/Control_53") (class "Default")
      (node (ref "U7") (pin "7") (pinfunction "OUT6_7") (pintype "passive"))
    )
    (net (code "56") (name "/Control_54") (class "Default")
      (node (ref "U7") (pin "8") (pinfunction "OUT7_8") (pintype "passive"))
    )
    (net (code "57") (name "/Control_55") (class "Default")
      (node (ref "U7") (pin "9") (pinfunction "OUT8_9") (pintype "passive"))
    )
    (net (code "58") (name "/Control_56") (class "Default")
      (node (ref "U8") (pin "2") (pinfunction "OUT1_2") (pintype "passive"))
    )
    (net (code "59") (name "/Control_57") (class "Default")
      (node (ref "U8") (pin "3") (pinfunction "OUT2_3") (pintype "passive"))
    )
    (net (code "60") (name "/Control_58") (class "Default")
      (node (ref "U8") (pin "4") (pinfunction "OUT3_4") (pintype "passive"))
    )
    (net (code "61") (name "/Control_59") (class "Default")
      (node (ref "U8") (pin "5") (pinfunction "OUT4_5") (pintype "passive"))
    )
    (net (code "62") (name "/Control_60") (class "Default")
      (node (ref "U8") (pin "6") (pinfunction "OUT5_6") (pintype "passive"))
    )
    (net (code "63") (name "/Control_61") (class "Default")
      (node (ref "U8") (pin "7") (pinfunction "OUT6_7") (pintype "passive"))
    )
    (net (code "64") (name "/Control_62") (class "Default")
      (node (ref "U8") (pin "8") (pinfunction "OUT7_8") (pintype "passive"))
    )
    (net (code "65") (name "/Control_63") (class "Default")
      (node (ref "U8") (pin "9") (pinfunction "OUT8_9") (pintype "passive"))
    )
    (net (code "66") (name "/Control_64") (class "Default")
      (node (ref "U9") (pin "2") (pinfunction "OUT1_2") (pintype "passive"))
    )
    (net (code "67") (name "/Control_65") (class "Default")
      (node (ref "U9") (pin "3") (pinfunction "OUT2_3") (pintype "passive"))
    )
    (net (code "68") (name "/Control_66") (class "Default")
      (node (ref "U9") (pin "4") (pinfunction "OUT3_4") (pintype "passive"))
    )
    (net (code "69") (name "/Control_67") (class "Default")
      (node (ref "U9") (pin "5") (pinfunction "OUT4_5") (pintype "passive"))
    )
    (net (code "70") (name "/Control_68") (class "Default")
      (node (ref "U9") (pin "6") (pinfunction "OUT5_6") (pintype "passive"))
    )
    (net (code "71") (name "/Control_69") (class "Default")
      (node (ref "U9") (pin "7") (pinfunction "OUT6_7") (pintype "passive"))
    )
    (net (code "72") (name "/Control_70") (class "Default")
      (node (ref "U9") (pin "8") (pinfunction "OUT7_8") (pintype "passive"))
    )
    (net (code "73") (name "/Control_71") (class "Default")
      (node (ref "U9") (pin "9") (pinfunction "OUT8_9") (pintype "passive"))
    )
    (net (code "74") (name "/Control_72") (class "Default")
      (node (ref "U12") (pin "2") (pinfunction "OUT1_2") (pintype "passive"))
    )
    (net (code "75") (name "/Control_73") (class "Default")
      (node (ref "U12") (pin "3") (pinfunction "OUT2_3") (pintype "passive"))
    )
    (net (code "76") (name "/Control_74") (class "Default")
      (node (ref "U12") (pin "4") (pinfunction "OUT3_4") (pintype "passive"))
    )
    (net (code "77") (name "/Control_75") (class "Default")
      (node (ref "U12") (pin "5") (pinfunction "OUT4_5") (pintype "passive"))
    )
    (net (code "78") (name "/Control_76") (class "Default")
      (node (ref "U12") (pin "6") (pinfunction "OUT5_6") (pintype "passive"))
    )
    (net (code "79") (name "/Control_77") (class "Default")
      (node (ref "U12") (pin "7") (pinfunction "OUT6_7") (pintype "passive"))
    )
    (net (code "80") (name "/Control_78") (class "Default")
      (node (ref "U12") (pin "8") (pinfunction "OUT7_8") (pintype "passive"))
    )
    (net (code "81") (name "/Control_79") (class "Default")
      (node (ref "U12") (pin "9") (pinfunction "OUT8_9") (pintype "passive"))
    )
    (net (code "82") (name "/Control_80") (class "Default")
      (node (ref "U14") (pin "2") (pinfunction "OUT1_2") (pintype "passive"))
    )
    (net (code "83") (name "/Control_81") (class "Default")
      (node (ref "U14") (pin "3") (pinfunction "OUT2_3") (pintype "passive"))
    )
    (net (code "84") (name "/Control_82") (class "Default")
      (node (ref "U14") (pin "4") (pinfunction "OUT3_4") (pintype "passive"))
    )
    (net (code "85") (name "/Control_83") (class "Default")
      (node (ref "U14") (pin "5") (pinfunction "OUT4_5") (pintype "passive"))
    )
    (net (code "86") (name "/Control_84") (class "Default")
      (node (ref "U14") (pin "6") (pinfunction "OUT5_6") (pintype "passive"))
    )
    (net (code "87") (name "/Control_85") (class "Default")
      (node (ref "U14") (pin "7") (pinfunction "OUT6_7") (pintype "passive"))
    )
    (net (code "88") (name "/Control_86") (class "Default")
      (node (ref "U14") (pin "8") (pinfunction "OUT7_8") (pintype "passive"))
    )
    (net (code "89") (name "/Control_87") (class "Default")
      (node (ref "U14") (pin "9") (pinfunction "OUT8_9") (pintype "passive"))
    )
    (net (code "90") (name "/Control_88") (class "Default")
      (node (ref "U15") (pin "2") (pinfunction "OUT1_2") (pintype "passive"))
    )
    (net (code "91") (name "/Control_89") (class "Default")
      (node (ref "U15") (pin "3") (pinfunction "OUT2_3") (pintype "passive"))
    )
    (net (code "92") (name "/Control_90") (class "Default")
      (node (ref "U15") (pin "4") (pinfunction "OUT3_4") (pintype "passive"))
    )
    (net (code "93") (name "/Control_91") (class "Default")
      (node (ref "U15") (pin "5") (pinfunction "OUT4_5") (pintype "passive"))
    )
    (net (code "94") (name "/Control_92") (class "Default")
      (node (ref "U15") (pin "6") (pinfunction "OUT5_6") (pintype "passive"))
    )
    (net (code "95") (name "/Control_93") (class "Default")
      (node (ref "U15") (pin "7") (pinfunction "OUT6_7") (pintype "passive"))
    )
    (net (code "96") (name "/Control_94") (class "Default")
      (node (ref "U15") (pin "8") (pinfunction "OUT7_8") (pintype "passive"))
    )
    (net (code "97") (name "/Control_95") (class "Default")
      (node (ref "U15") (pin "9") (pinfunction "OUT8_9") (pintype "passive"))
    )
    (net (code "98") (name "/Control_96") (class "Default")
      (node (ref "U16") (pin "2") (pinfunction "OUT1_2") (pintype "passive"))
    )
    (net (code "99") (name "/Control_97") (class "Default")
      (node (ref "U16") (pin "3") (pinfunction "OUT2_3") (pintype "passive"))
    )
    (net (code "100") (name "/Control_98") (class "Default")
      (node (ref "U16") (pin "4") (pinfunction "OUT3_4") (pintype "passive"))
    )
    (net (code "101") (name "/Control_99") (class "Default")
      (node (ref "U16") (pin "5") (pinfunction "OUT4_5") (pintype "passive"))
    )
    (net (code "102") (name "/Control_100") (class "Default")
      (node (ref "U16") (pin "6") (pinfunction "OUT5_6") (pintype "passive"))
    )
    (net (code "103") (name "/Control_101") (class "Default")
      (node (ref "U16") (pin "7") (pinfunction "OUT6_7") (pintype "passive"))
    )
    (net (code "104") (name "/Control_102") (class "Default")
      (node (ref "U16") (pin "8") (pinfunction "OUT7_8") (pintype "passive"))
    )
    (net (code "105") (name "/Control_103") (class "Default")
      (node (ref "U16") (pin "9") (pinfunction "OUT8_9") (pintype "passive"))
    )
    (net (code "106") (name "/Control_104") (class "Default")
      (node (ref "U17") (pin "2") (pinfunction "OUT1_2") (pintype "passive"))
    )
    (net (code "107") (name "/Control_105") (class "Default")
      (node (ref "U17") (pin "3") (pinfunction "OUT2_3") (pintype "passive"))
    )
    (net (code "108") (name "/Control_106") (class "Default")
      (node (ref "U17") (pin "4") (pinfunction "OUT3_4") (pintype "passive"))
    )
    (net (code "109") (name "/Control_107") (class "Default")
      (node (ref "U17") (pin "5") (pinfunction "OUT4_5") (pintype "passive"))
    )
    (net (code "110") (name "/Control_108") (class "Default")
      (node (ref "U17") (pin "6") (pinfunction "OUT5_6") (pintype "passive"))
    )
    (net (code "111") (name "/Control_109") (class "Default")
      (node (ref "U17") (pin "7") (pinfunction "OUT6_7") (pintype "passive"))
    )
    (net (code "112") (name "/Control_110") (class "Default")
      (node (ref "U17") (pin "8") (pinfunction "OUT7_8") (pintype "passive"))
    )
    (net (code "113") (name "/Control_111") (class "Default")
      (node (ref "U17") (pin "9") (pinfunction "OUT8_9") (pintype "passive"))
    )
    (net (code "114") (name "/Control_112") (class "Default")
      (node (ref "U18") (pin "2") (pinfunction "OUT1_2") (pintype "passive"))
    )
    (net (code "115") (name "/Control_113") (class "Default")
      (node (ref "U18") (pin "3") (pinfunction "OUT2_3") (pintype "passive"))
    )
    (net (code "116") (name "/Control_114") (class "Default")
      (node (ref "U18") (pin "4") (pinfunction "OUT3_4") (pintype "passive"))
    )
    (net (code "117") (name "/Control_115") (class "Default")
      (node (ref "U18") (pin "5") (pinfunction "OUT4_5") (pintype "passive"))
    )
    (net (code "118") (name "/Control_116") (class "Default")
      (node (ref "U18") (pin "6") (pinfunction "OUT5_6") (pintype "passive"))
    )
    (net (code "119") (name "/Control_117") (class "Default")
      (node (ref "U18") (pin "7") (pinfunction "OUT6_7") (pintype "passive"))
    )
    (net (code "120") (name "/Control_118") (class "Default")
      (node (ref "U18") (pin "8") (pinfunction "OUT7_8") (pintype "passive"))
    )
    (net (code "121") (name "/Control_119") (class "Default")
      (node (ref "U18") (pin "9") (pinfunction "OUT8_9") (pintype "passive"))
    )
    (net (code "122") (name "/Control_120") (class "Default")
      (node (ref "U19") (pin "2") (pinfunction "OUT1_2") (pintype "passive"))
    )
    (net (code "123") (name "/Control_121") (class "Default")
      (node (ref "U19") (pin "3") (pinfunction "OUT2_3") (pintype "passive"))
    )
    (net (code "124") (name "/Control_122") (class "Default")
      (node (ref "U19") (pin "4") (pinfunction "OUT3_4") (pintype "passive"))
    )
    (net (code "125") (name "/Control_123") (class "Default")
      (node (ref "U19") (pin "5") (pinfunction "OUT4_5") (pintype "passive"))
    )
    (net (code "126") (name "/Control_124") (class "Default")
      (node (ref "U19") (pin "6") (pinfunction "OUT5_6") (pintype "passive"))
    )
    (net (code "127") (name "/Control_125") (class "Default")
      (node (ref "U19") (pin "7") (pinfunction "OUT6_7") (pintype "passive"))
    )
    (net (code "128") (name "/Control_126") (class "Default")
      (node (ref "U19") (pin "8") (pinfunction "OUT7_8") (pintype "passive"))
    )
    (net (code "129") (name "/Control_127") (class "Default")
      (node (ref "U19") (pin "9") (pinfunction "OUT8_9") (pintype "passive"))
    )
    (net (code "130") (name "/Control_128") (class "Default")
      (node (ref "U20") (pin "2") (pinfunction "OUT1_2") (pintype "passive"))
    )
    (net (code "131") (name "/Control_129") (class "Default")
      (node (ref "U20") (pin "3") (pinfunction "OUT2_3") (pintype "passive"))
    )
    (net (code "132") (name "/Control_130") (class "Default")
      (node (ref "U20") (pin "4") (pinfunction "OUT3_4") (pintype "passive"))
    )
    (net (code "133") (name "/Control_131") (class "Default")
      (node (ref "U20") (pin "5") (pinfunction "OUT4_5") (pintype "passive"))
    )
    (net (code "134") (name "/Control_132") (class "Default")
      (node (ref "U20") (pin "6") (pinfunction "OUT5_6") (pintype "passive"))
    )
    (net (code "135") (name "/Control_133") (class "Default")
      (node (ref "U20") (pin "7") (pinfunction "OUT6_7") (pintype "passive"))
    )
    (net (code "136") (name "/Control_134") (class "Default")
      (node (ref "U20") (pin "8") (pinfunction "OUT7_8") (pintype "passive"))
    )
    (net (code "137") (name "/Control_135") (class "Default")
      (node (ref "U20") (pin "9") (pinfunction "OUT8_9") (pintype "passive"))
    )
    (net (code "138") (name "/Control_136") (class "Default")
      (node (ref "U21") (pin "2") (pinfunction "OUT1_2") (pintype "passive"))
    )
    (net (code "139") (name "/Control_137") (class "Default")
      (node (ref "U21") (pin "3") (pinfunction "OUT2_3") (pintype "passive"))
    )
    (net (code "140") (name "/Control_138") (class "Default")
      (node (ref "U21") (pin "4") (pinfunction "OUT3_4") (pintype "passive"))
    )
    (net (code "141") (name "/Control_139") (class "Default")
      (node (ref "U21") (pin "5") (pinfunction "OUT4_5") (pintype "passive"))
    )
    (net (code "142") (name "/Control_140") (class "Default")
      (node (ref "U21") (pin "6") (pinfunction "OUT5_6") (pintype "passive"))
    )
    (net (code "143") (name "/Control_141") (class "Default")
      (node (ref "U21") (pin "7") (pinfunction "OUT6_7") (pintype "passive"))
    )
    (net (code "144") (name "/Control_142") (class "Default")
      (node (ref "U21") (pin "8") (pinfunction "OUT7_8") (pintype "passive"))
    )
    (net (code "145") (name "/Control_143") (class "Default")
      (node (ref "U21") (pin "9") (pinfunction "OUT8_9") (pintype "passive"))
    )
    (net (code "147") (name "/EN") (class "Default")
      (node (ref "P41") (pin "25") (pinfunction "25_25") (pintype "passive"))
      (node (ref "U1") (pin "12") (pinfunction "EN1_12") (pintype "passive"))
      (node (ref "U12") (pin "12") (pinfunction "EN1_12") (pintype "passive"))
      (node (ref "U14") (pin "12") (pinfunction "EN1_12") (pintype "passive"))
      (node (ref "U15") (pin "12") (pinfunction "EN1_12") (pintype "passive"))
      (node (ref "U16") (pin "12") (pinfunction "EN1_12") (pintype "passive"))
      (node (ref "U17") (pin "12") (pinfunction "EN1_12") (pintype "passive"))
      (node (ref "U18") (pin "12") (pinfunction "EN1_12") (pintype "passive"))
      (node (ref "U19") (pin "12") (pinfunction "EN1_12") (pintype "passive"))
      (node (ref "U2") (pin "12") (pinfunction "EN1_12") (pintype "passive"))
      (node (ref "U20") (pin "12") (pinfunction "EN1_12") (pintype "passive"))
      (node (ref "U21") (pin "12") (pinfunction "EN1_12") (pintype "passive"))
      (node (ref "U3") (pin "12") (pinfunction "EN1_12") (pintype "passive"))
      (node (ref "U4") (pin "12") (pinfunction "EN1_12") (pintype "passive"))
      (node (ref "U5") (pin "12") (pinfunction "EN1_12") (pintype "passive"))
      (node (ref "U6") (pin "12") (pinfunction "EN1_12") (pintype "passive"))
      (node (ref "U7") (pin "12") (pinfunction "EN1_12") (pintype "passive"))
      (node (ref "U8") (pin "12") (pinfunction "EN1_12") (pintype "passive"))
      (node (ref "U9") (pin "12") (pinfunction "EN1_12") (pintype "passive"))
    )
    (net (code "148") (name "/NCS0") (class "Default")
      (node (ref "P41") (pin "3") (pinfunction "3_3") (pintype "passive"))
      (node (ref "U1") (pin "16") (pinfunction "NCS_16") (pintype "passive"))
    )
    (net (code "149") (name "/NCS1") (class "Default")
      (node (ref "P41") (pin "4") (pinfunction "4_4") (pintype "passive"))
      (node (ref "U2") (pin "16") (pinfunction "NCS_16") (pintype "passive"))
    )
    (net (code "150") (name "/NCS2") (class "Default")
      (node (ref "P41") (pin "5") (pinfunction "5_5") (pintype "passive"))
      (node (ref "U3") (pin "16") (pinfunction "NCS_16") (pintype "passive"))
    )
    (net (code "151") (name "/NCS3") (class "Default")
      (node (ref "P41") (pin "6") (pinfunction "6_6") (pintype "passive"))
      (node (ref "U4") (pin "16") (pinfunction "NCS_16") (pintype "passive"))
    )
    (net (code "152") (name "/NCS4") (class "Default")
      (node (ref "P41") (pin "7") (pinfunction "7_7") (pintype "passive"))
      (node (ref "U5") (pin "16") (pinfunction "NCS_16") (pintype "passive"))
    )
    (net (code "153") (name "/NCS5") (class "Default")
      (node (ref "P41") (pin "8") (pinfunction "8_8") (pintype "passive"))
      (node (ref "U6") (pin "16") (pinfunction "NCS_16") (pintype "passive"))
    )
    (net (code "154") (name "/NCS6") (class "Default")
      (node (ref "P41") (pin "9") (pinfunction "9_9") (pintype "passive"))
      (node (ref "U7") (pin "16") (pinfunction "NCS_16") (pintype "passive"))
    )
    (net (code "155") (name "/NCS7") (class "Default")
      (node (ref "P41") (pin "10") (pinfunction "10_10") (pintype "passive"))
      (node (ref "U8") (pin "16") (pinfunction "NCS_16") (pintype "passive"))
    )
    (net (code "156") (name "/NCS8") (class "Default")
      (node (ref "P41") (pin "11") (pinfunction "11_11") (pintype "passive"))
      (node (ref "U9") (pin "16") (pinfunction "NCS_16") (pintype "passive"))
    )
    (net (code "157") (name "/NCS9") (class "Default")
      (node (ref "P41") (pin "12") (pinfunction "12_12") (pintype "passive"))
      (node (ref "U12") (pin "16") (pinfunction "NCS_16") (pintype "passive"))
    )
    (net (code "158") (name "/NCS10") (class "Default")
      (node (ref "P41") (pin "13") (pinfunction "13_13") (pintype "passive"))
      (node (ref "U14") (pin "16") (pinfunction "NCS_16") (pintype "passive"))
    )
    (net (code "159") (name "/NCS11") (class "Default")
      (node (ref "P41") (pin "14") (pinfunction "14_14") (pintype "passive"))
      (node (ref "U15") (pin "16") (pinfunction "NCS_16") (pintype "passive"))
    )
    (net (code "160") (name "/NCS12") (class "Default")
      (node (ref "P41") (pin "15") (pinfunction "15_15") (pintype "passive"))
      (node (ref "U16") (pin "16") (pinfunction "NCS_16") (pintype "passive"))
    )
    (net (code "161") (name "/NCS13") (class "Default")
      (node (ref "P41") (pin "16") (pinfunction "16_16") (pintype "passive"))
      (node (ref "U17") (pin "16") (pinfunction "NCS_16") (pintype "passive"))
    )
    (net (code "162") (name "/NCS14") (class "Default")
      (node (ref "P41") (pin "17") (pinfunction "17_17") (pintype "passive"))
      (node (ref "U18") (pin "16") (pinfunction "NCS_16") (pintype "passive"))
    )
    (net (code "163") (name "/NCS15") (class "Default")
      (node (ref "P41") (pin "18") (pinfunction "18_18") (pintype "passive"))
      (node (ref "U19") (pin "16") (pinfunction "NCS_16") (pintype "passive"))
    )
    (net (code "164") (name "/NCS16") (class "Default")
      (node (ref "P41") (pin "19") (pinfunction "19_19") (pintype "passive"))
      (node (ref "U20") (pin "16") (pinfunction "NCS_16") (pintype "passive"))
    )
    (net (code "165") (name "/NCS17") (class "Default")
      (node (ref "P41") (pin "20") (pinfunction "20_20") (pintype "passive"))
      (node (ref "U21") (pin "16") (pinfunction "NCS_16") (pintype "passive"))
    )
    (net (code "166") (name "/SCLK") (class "Default")
      (node (ref "P41") (pin "23") (pinfunction "23_23") (pintype "passive"))
      (node (ref "U1") (pin "17") (pinfunction "SCLK_17") (pintype "passive"))
      (node (ref "U12") (pin "17") (pinfunction "SCLK_17") (pintype "passive"))
      (node (ref "U14") (pin "17") (pinfunction "SCLK_17") (pintype "passive"))
      (node (ref "U15") (pin "17") (pinfunction "SCLK_17") (pintype "passive"))
      (node (ref "U16") (pin "17") (pinfunction "SCLK_17") (pintype "passive"))
      (node (ref "U17") (pin "17") (pinfunction "SCLK_17") (pintype "passive"))
      (node (ref "U18") (pin "17") (pinfunction "SCLK_17") (pintype "passive"))
      (node (ref "U19") (pin "17") (pinfunction "SCLK_17") (pintype "passive"))
      (node (ref "U2") (pin "17") (pinfunction "SCLK_17") (pintype "passive"))
      (node (ref "U20") (pin "17") (pinfunction "SCLK_17") (pintype "passive"))
      (node (ref "U21") (pin "17") (pinfunction "SCLK_17") (pintype "passive"))
      (node (ref "U3") (pin "17") (pinfunction "SCLK_17") (pintype "passive"))
      (node (ref "U4") (pin "17") (pinfunction "SCLK_17") (pintype "passive"))
      (node (ref "U5") (pin "17") (pinfunction "SCLK_17") (pintype "passive"))
      (node (ref "U6") (pin "17") (pinfunction "SCLK_17") (pintype "passive"))
      (node (ref "U7") (pin "17") (pinfunction "SCLK_17") (pintype "passive"))
      (node (ref "U8") (pin "17") (pinfunction "SCLK_17") (pintype "passive"))
      (node (ref "U9") (pin "17") (pinfunction "SCLK_17") (pintype "passive"))
    )
    (net (code "167") (name "/SIN") (class "Default")
      (node (ref "P41") (pin "24") (pinfunction "24_24") (pintype "passive"))
      (node (ref "U1") (pin "15") (pinfunction "MOSI_15") (pintype "passive"))
      (node (ref "U12") (pin "15") (pinfunction "MOSI_15") (pintype "passive"))
      (node (ref "U14") (pin "15") (pinfunction "MOSI_15") (pintype "passive"))
      (node (ref "U15") (pin "15") (pinfunction "MOSI_15") (pintype "passive"))
      (node (ref "U16") (pin "15") (pinfunction "MOSI_15") (pintype "passive"))
      (node (ref "U17") (pin "15") (pinfunction "MOSI_15") (pintype "passive"))
      (node (ref "U18") (pin "15") (pinfunction "MOSI_15") (pintype "passive"))
      (node (ref "U19") (pin "15") (pinfunction "MOSI_15") (pintype "passive"))
      (node (ref "U2") (pin "15") (pinfunction "MOSI_15") (pintype "passive"))
      (node (ref "U20") (pin "15") (pinfunction "MOSI_15") (pintype "passive"))
      (node (ref "U21") (pin "15") (pinfunction "MOSI_15") (pintype "passive"))
      (node (ref "U3") (pin "15") (pinfunction "MOSI_15") (pintype "passive"))
      (node (ref "U4") (pin "15") (pinfunction "MOSI_15") (pintype "passive"))
      (node (ref "U5") (pin "15") (pinfunction "MOSI_15") (pintype "passive"))
      (node (ref "U6") (pin "15") (pinfunction "MOSI_15") (pintype "passive"))
      (node (ref "U7") (pin "15") (pinfunction "MOSI_15") (pintype "passive"))
      (node (ref "U8") (pin "15") (pinfunction "MOSI_15") (pintype "passive"))
      (node (ref "U9") (pin "15") (pinfunction "MOSI_15") (pintype "passive"))
    )
    (net (code "168") (name "12V") (class "Default")
      (node (ref "C10") (pin "1") (pinfunction "1_1") (pintype "passive"))
      (node (ref "C12") (pin "1") (pinfunction "1_1") (pintype "passive"))
      (node (ref "C13") (pin "1") (pinfunction "1_1") (pintype "passive"))
      (node (ref "C14") (pin "1") (pinfunction "1_1") (pintype "passive"))
      (node (ref "C15") (pin "1") (pinfunction "1_1") (pintype "passive"))
      (node (ref "C5") (pin "1") (pinfunction "1_1") (pintype "passive"))
      (node (ref "J25") (pin "1") (pinfunction "1_1") (pintype "passive"))
      (node (ref "P41") (pin "2") (pinfunction "2_2") (pintype "passive"))
      (node (ref "R145") (pin "2") (pinfunction "2_2") (pintype "passive"))
      (node (ref "R146") (pin "2") (pinfunction "2_2") (pintype "passive"))
      (node (ref "R147") (pin "2") (pinfunction "2_2") (pintype "passive"))
      (node (ref "R148") (pin "2") (pinfunction "2_2") (pintype "passive"))
      (node (ref "R149") (pin "2") (pinfunction "2_2") (pintype "passive"))
      (node (ref "R150") (pin "2") (pinfunction "2_2") (pintype "passive"))
      (node (ref "R151") (pin "2") (pinfunction "2_2") (pintype "passive"))
      (node (ref "R152") (pin "2") (pinfunction "2_2") (pintype "passive"))
      (node (ref "R153") (pin "2") (pinfunction "2_2") (pintype "passive"))
      (node (ref "R154") (pin "2") (pinfunction "2_2") (pintype "passive"))
      (node (ref "R155") (pin "2") (pinfunction "2_2") (pintype "passive"))
      (node (ref "R156") (pin "2") (pinfunction "2_2") (pintype "passive"))
      (node (ref "R157") (pin "2") (pinfunction "2_2") (pintype "passive"))
      (node (ref "R158") (pin "2") (pinfunction "2_2") (pintype "passive"))
      (node (ref "R159") (pin "2") (pinfunction "2_2") (pintype "passive"))
      (node (ref "R160") (pin "2") (pinfunction "2_2") (pintype "passive"))
      (node (ref "R161") (pin "2") (pinfunction "2_2") (pintype "passive"))
      (node (ref "R162") (pin "2") (pinfunction "2_2") (pintype "passive"))
    )
    (net (code "169") (name "GND") (class "Default")
      (node (ref "C1") (pin "1") (pinfunction "1_1") (pintype "passive"))
      (node (ref "C10") (pin "2") (pinfunction "2_2") (pintype "passive"))
      (node (ref "C11") (pin "1") (pinfunction "1_1") (pintype "passive"))
      (node (ref "C12") (pin "2") (pinfunction "2_2") (pintype "passive"))
      (node (ref "C13") (pin "2") (pinfunction "2_2") (pintype "passive"))
      (node (ref "C14") (pin "2") (pinfunction "2_2") (pintype "passive"))
      (node (ref "C15") (pin "2") (pinfunction "2_2") (pintype "passive"))
      (node (ref "C2") (pin "1") (pinfunction "1_1") (pintype "passive"))
      (node (ref "C24") (pin "1") (pinfunction "1_1") (pintype "passive"))
      (node (ref "C3") (pin "1") (pinfunction "1_1") (pintype "passive"))
      (node (ref "C36") (pin "1") (pinfunction "1_1") (pintype "passive"))
      (node (ref "C37") (pin "1") (pinfunction "1_1") (pintype "passive"))
      (node (ref "C38") (pin "1") (pinfunction "1_1") (pintype "passive"))
      (node (ref "C39") (pin "1") (pinfunction "1_1") (pintype "passive"))
      (node (ref "C4") (pin "1") (pinfunction "1_1") (pintype "passive"))
      (node (ref "C40") (pin "1") (pinfunction "1_1") (pintype "passive"))
      (node (ref "C41") (pin "1") (pinfunction "1_1") (pintype "passive"))
      (node (ref "C42") (pin "1") (pinfunction "1_1") (pintype "passive"))
      (node (ref "C43") (pin "1") (pinfunction "1_1") (pintype "passive"))
      (node (ref "C44") (pin "1") (pinfunction "1_1") (pintype "passive"))
      (node (ref "C45") (pin "1") (pinfunction "1_1") (pintype "passive"))
      (node (ref "C46") (pin "1") (pinfunction "1_1") (pintype "passive"))
      (node (ref "C47") (pin "1") (pinfunction "1_1") (pintype "passive"))
      (node (ref "C48") (pin "1") (pinfunction "1_1") (pintype "passive"))
      (node (ref "C49") (pin "1") (pinfunction "1_1") (pintype "passive"))
      (node (ref "C5") (pin "2") (pinfunction "2_2") (pintype "passive"))
      (node (ref "C50") (pin "1") (pinfunction "1_1") (pintype "passive"))
      (node (ref "C51") (pin "1") (pinfunction "1_1") (pintype "passive"))
      (node (ref "C52") (pin "1") (pinfunction "1_1") (pintype "passive"))
      (node (ref "C53") (pin "1") (pinfunction "1_1") (pintype "passive"))
      (node (ref "C54") (pin "1") (pinfunction "1_1") (pintype "passive"))
      (node (ref "C55") (pin "1") (pinfunction "1_1") (pintype "passive"))
      (node (ref "C56") (pin "1") (pinfunction "1_1") (pintype "passive"))
      (node (ref "C57") (pin "1") (pinfunction "1_1") (pintype "passive"))
      (node (ref "C58") (pin "1") (pinfunction "1_1") (pintype "passive"))
      (node (ref "C59") (pin "1") (pinfunction "1_1") (pintype "passive"))
      (node (ref "C6") (pin "1") (pinfunction "1_1") (pintype "passive"))
      (node (ref "C60") (pin "1") (pinfunction "1_1") (pintype "passive"))
      (node (ref "C61") (pin "1") (pinfunction "1_1") (pintype "passive"))
      (node (ref "C62") (pin "1") (pinfunction "1_1") (pintype "passive"))
      (node (ref "C63") (pin "1") (pinfunction "1_1") (pintype "passive"))
      (node (ref "C64") (pin "1") (pinfunction "1_1") (pintype "passive"))
      (node (ref "C65") (pin "1") (pinfunction "1_1") (pintype "passive"))
      (node (ref "C66") (pin "1") (pinfunction "1_1") (pintype "passive"))
      (node (ref "C67") (pin "1") (pinfunction "1_1") (pintype "passive"))
      (node (ref "C68") (pin "1") (pinfunction "1_1") (pintype "passive"))
      (node (ref "C69") (pin "1") (pinfunction "1_1") (pintype "passive"))
      (node (ref "C7") (pin "1") (pinfunction "1_1") (pintype "passive"))
      (node (ref "C70") (pin "1") (pinfunction "1_1") (pintype "passive"))
      (node (ref "C71") (pin "1") (pinfunction "1_1") (pintype "passive"))
      (node (ref "C72") (pin "1") (pinfunction "1_1") (pintype "passive"))
      (node (ref "C73") (pin "1") (pinfunction "1_1") (pintype "passive"))
      (node (ref "C74") (pin "1") (pinfunction "1_1") (pintype "passive"))
      (node (ref "C75") (pin "1") (pinfunction "1_1") (pintype "passive"))
      (node (ref "C76") (pin "1") (pinfunction "1_1") (pintype "passive"))
      (node (ref "C77") (pin "1") (pinfunction "1_1") (pintype "passive"))
      (node (ref "C78") (pin "1") (pinfunction "1_1") (pintype "passive"))
      (node (ref "C79") (pin "1") (pinfunction "1_1") (pintype "passive"))
      (node (ref "C8") (pin "1") (pinfunction "1_1") (pintype "passive"))
      (node (ref "C9") (pin "1") (pinfunction "1_1") (pintype "passive"))
      (node (ref "J26") (pin "1") (pinfunction "1_1") (pintype "passive"))
      (node (ref "P41") (pin "1") (pinfunction "1_1") (pintype "passive"))
      (node (ref "P41") (pin "21") (pinfunction "21_21") (pintype "passive"))
      (node (ref "P41") (pin "22") (pinfunction "22_22") (pintype "passive"))
      (node (ref "U1") (pin "10") (pinfunction "GND_10") (pintype "passive"))
      (node (ref "U1") (pin "21") (pinfunction "PAD_21") (pintype "passive"))
      (node (ref "U12") (pin "10") (pinfunction "GND_10") (pintype "passive"))
      (node (ref "U12") (pin "21") (pinfunction "PAD_21") (pintype "passive"))
      (node (ref "U14") (pin "10") (pinfunction "GND_10") (pintype "passive"))
      (node (ref "U14") (pin "21") (pinfunction "PAD_21") (pintype "passive"))
      (node (ref "U15") (pin "10") (pinfunction "GND_10") (pintype "passive"))
      (node (ref "U15") (pin "21") (pinfunction "PAD_21") (pintype "passive"))
      (node (ref "U16") (pin "10") (pinfunction "GND_10") (pintype "passive"))
      (node (ref "U16") (pin "21") (pinfunction "PAD_21") (pintype "passive"))
      (node (ref "U17") (pin "10") (pinfunction "GND_10") (pintype "passive"))
      (node (ref "U17") (pin "21") (pinfunction "PAD_21") (pintype "passive"))
      (node (ref "U18") (pin "10") (pinfunction "GND_10") (pintype "passive"))
      (node (ref "U18") (pin "21") (pinfunction "PAD_21") (pintype "passive"))
      (node (ref "U19") (pin "10") (pinfunction "GND_10") (pintype "passive"))
      (node (ref "U19") (pin "21") (pinfunction "PAD_21") (pintype "passive"))
      (node (ref "U2") (pin "10") (pinfunction "GND_10") (pintype "passive"))
      (node (ref "U2") (pin "21") (pinfunction "PAD_21") (pintype "passive"))
      (node (ref "U20") (pin "10") (pinfunction "GND_10") (pintype "passive"))
      (node (ref "U20") (pin "21") (pinfunction "PAD_21") (pintype "passive"))
      (node (ref "U21") (pin "10") (pinfunction "GND_10") (pintype "passive"))
      (node (ref "U21") (pin "21") (pinfunction "PAD_21") (pintype "passive"))
      (node (ref "U3") (pin "10") (pinfunction "GND_10") (pintype "passive"))
      (node (ref "U3") (pin "21") (pinfunction "PAD_21") (pintype "passive"))
      (node (ref "U4") (pin "10") (pinfunction "GND_10") (pintype "passive"))
      (node (ref "U4") (pin "21") (pinfunction "PAD_21") (pintype "passive"))
      (node (ref "U5") (pin "10") (pinfunction "GND_10") (pintype "passive"))
      (node (ref "U5") (pin "21") (pinfunction "PAD_21") (pintype "passive"))
      (node (ref "U6") (pin "10") (pinfunction "GND_10") (pintype "passive"))
      (node (ref "U6") (pin "21") (pinfunction "PAD_21") (pintype "passive"))
      (node (ref "U7") (pin "10") (pinfunction "GND_10") (pintype "passive"))
      (node (ref "U7") (pin "21") (pinfunction "PAD_21") (pintype "passive"))
      (node (ref "U8") (pin "10") (pinfunction "GND_10") (pintype "passive"))
      (node (ref "U8") (pin "21") (pinfunction "PAD_21") (pintype "passive"))
      (node (ref "U9") (pin "10") (pinfunction "GND_10") (pintype "passive"))
      (node (ref "U9") (pin "21") (pinfunction "PAD_21") (pintype "passive"))
    )
    (net (code "170") (name "Net-(U1-5V)") (class "Default")
      (node (ref "C6") (pin "2") (pinfunction "2_2") (pintype "passive"))
      (node (ref "U1") (pin "18") (pinfunction "5V_18") (pintype "passive"))
    )
    (net (code "171") (name "Net-(U1-BO)") (class "Default")
      (node (ref "P4") (pin "1") (pinfunction "1_1") (pintype "passive"))
      (node (ref "U1") (pin "20") (pinfunction "BO_20") (pintype "passive"))
    )
    (net (code "172") (name "Net-(U1-Rdelay)") (class "Default")
      (node (ref "C11") (pin "2") (pinfunction "2_2") (pintype "passive"))
      (node (ref "U1") (pin "13") (pinfunction "Rdelay_13") (pintype "passive"))
    )
    (net (code "173") (name "Net-(U1-Vin)") (class "Default")
      (node (ref "C1") (pin "2") (pinfunction "2_2") (pintype "passive"))
      (node (ref "R145") (pin "1") (pinfunction "1_1") (pintype "passive"))
      (node (ref "U1") (pin "19") (pinfunction "Vin_19") (pintype "passive"))
    )
    (net (code "174") (name "Net-(U1-~{RST})") (class "Default")
      (node (ref "P8") (pin "1") (pinfunction "1_1") (pintype "passive"))
      (node (ref "U1") (pin "14") (pinfunction "~{RST}_14") (pintype "passive"))
    )
    (net (code "175") (name "Net-(U2-5V)") (class "Default")
      (node (ref "C7") (pin "2") (pinfunction "2_2") (pintype "passive"))
      (node (ref "U2") (pin "18") (pinfunction "5V_18") (pintype "passive"))
    )
    (net (code "176") (name "Net-(U2-BO)") (class "Default")
      (node (ref "P5") (pin "1") (pinfunction "1_1") (pintype "passive"))
      (node (ref "U2") (pin "20") (pinfunction "BO_20") (pintype "passive"))
    )
    (net (code "177") (name "Net-(U2-Rdelay)") (class "Default")
      (node (ref "C24") (pin "2") (pinfunction "2_2") (pintype "passive"))
      (node (ref "U2") (pin "13") (pinfunction "Rdelay_13") (pintype "passive"))
    )
    (net (code "178") (name "Net-(U2-Vin)") (class "Default")
      (node (ref "C2") (pin "2") (pinfunction "2_2") (pintype "passive"))
      (node (ref "R146") (pin "1") (pinfunction "1_1") (pintype "passive"))
      (node (ref "U2") (pin "19") (pinfunction "Vin_19") (pintype "passive"))
    )
    (net (code "179") (name "Net-(U2-~{RST})") (class "Default")
      (node (ref "P9") (pin "1") (pinfunction "1_1") (pintype "passive"))
      (node (ref "U2") (pin "14") (pinfunction "~{RST}_14") (pintype "passive"))
    )
    (net (code "180") (name "Net-(U3-5V)") (class "Default")
      (node (ref "C8") (pin "2") (pinfunction "2_2") (pintype "passive"))
      (node (ref "U3") (pin "18") (pinfunction "5V_18") (pintype "passive"))
    )
    (net (code "181") (name "Net-(U3-BO)") (class "Default")
      (node (ref "P6") (pin "1") (pinfunction "1_1") (pintype "passive"))
      (node (ref "U3") (pin "20") (pinfunction "BO_20") (pintype "passive"))
    )
    (net (code "182") (name "Net-(U3-Rdelay)") (class "Default")
      (node (ref "C36") (pin "2") (pinfunction "2_2") (pintype "passive"))
      (node (ref "U3") (pin "13") (pinfunction "Rdelay_13") (pintype "passive"))
    )
    (net (code "183") (name "Net-(U3-Vin)") (class "Default")
      (node (ref "C3") (pin "2") (pinfunction "2_2") (pintype "passive"))
      (node (ref "R147") (pin "1") (pinfunction "1_1") (pintype "passive"))
      (node (ref "U3") (pin "19") (pinfunction "Vin_19") (pintype "passive"))
    )
    (net (code "184") (name "Net-(U3-~{RST})") (class "Default")
      (node (ref "P10") (pin "1") (pinfunction "1_1") (pintype "passive"))
      (node (ref "U3") (pin "14") (pinfunction "~{RST}_14") (pintype "passive"))
    )
    (net (code "185") (name "Net-(U4-5V)") (class "Default")
      (node (ref "C9") (pin "2") (pinfunction "2_2") (pintype "passive"))
      (node (ref "U4") (pin "18") (pinfunction "5V_18") (pintype "passive"))
    )
    (net (code "186") (name "Net-(U4-BO)") (class "Default")
      (node (ref "P7") (pin "1") (pinfunction "1_1") (pintype "passive"))
      (node (ref "U4") (pin "20") (pinfunction "BO_20") (pintype "passive"))
    )
    (net (code "187") (name "Net-(U4-Rdelay)") (class "Default")
      (node (ref "C37") (pin "2") (pinfunction "2_2") (pintype "passive"))
      (node (ref "U4") (pin "13") (pinfunction "Rdelay_13") (pintype "passive"))
    )
    (net (code "188") (name "Net-(U4-Vin)") (class "Default")
      (node (ref "C4") (pin "2") (pinfunction "2_2") (pintype "passive"))
      (node (ref "R148") (pin "1") (pinfunction "1_1") (pintype "passive"))
      (node (ref "U4") (pin "19") (pinfunction "Vin_19") (pintype "passive"))
    )
    (net (code "189") (name "Net-(U4-~{RST})") (class "Default")
      (node (ref "P11") (pin "1") (pinfunction "1_1") (pintype "passive"))
      (node (ref "U4") (pin "14") (pinfunction "~{RST}_14") (pintype "passive"))
    )
    (net (code "190") (name "Net-(U5-5V)") (class "Default")
      (node (ref "C42") (pin "2") (pinfunction "2_2") (pintype "passive"))
      (node (ref "U5") (pin "18") (pinfunction "5V_18") (pintype "passive"))
    )
    (net (code "191") (name "Net-(U5-BO)") (class "Default")
      (node (ref "P12") (pin "1") (pinfunction "1_1") (pintype "passive"))
      (node (ref "U5") (pin "20") (pinfunction "BO_20") (pintype "passive"))
    )
    (net (code "192") (name "Net-(U5-Rdelay)") (class "Default")
      (node (ref "C46") (pin "2") (pinfunction "2_2") (pintype "passive"))
      (node (ref "U5") (pin "13") (pinfunction "Rdelay_13") (pintype "passive"))
    )
    (net (code "193") (name "Net-(U5-Vin)") (class "Default")
      (node (ref "C38") (pin "2") (pinfunction "2_2") (pintype "passive"))
      (node (ref "R149") (pin "1") (pinfunction "1_1") (pintype "passive"))
      (node (ref "U5") (pin "19") (pinfunction "Vin_19") (pintype "passive"))
    )
    (net (code "194") (name "Net-(U5-~{RST})") (class "Default")
      (node (ref "P16") (pin "1") (pinfunction "1_1") (pintype "passive"))
      (node (ref "U5") (pin "14") (pinfunction "~{RST}_14") (pintype "passive"))
    )
    (net (code "195") (name "Net-(U6-5V)") (class "Default")
      (node (ref "C43") (pin "2") (pinfunction "2_2") (pintype "passive"))
      (node (ref "U6") (pin "18") (pinfunction "5V_18") (pintype "passive"))
    )
    (net (code "196") (name "Net-(U6-BO)") (class "Default")
      (node (ref "P13") (pin "1") (pinfunction "1_1") (pintype "passive"))
      (node (ref "U6") (pin "20") (pinfunction "BO_20") (pintype "passive"))
    )
    (net (code "197") (name "Net-(U6-Rdelay)") (class "Default")
      (node (ref "C47") (pin "2") (pinfunction "2_2") (pintype "passive"))
      (node (ref "U6") (pin "13") (pinfunction "Rdelay_13") (pintype "passive"))
    )
    (net (code "198") (name "Net-(U6-Vin)") (class "Default")
      (node (ref "C39") (pin "2") (pinfunction "2_2") (pintype "passive"))
      (node (ref "R150") (pin "1") (pinfunction "1_1") (pintype "passive"))
      (node (ref "U6") (pin "19") (pinfunction "Vin_19") (pintype "passive"))
    )
    (net (code "199") (name "Net-(U6-~{RST})") (class "Default")
      (node (ref "P17") (pin "1") (pinfunction "1_1") (pintype "passive"))
      (node (ref "U6") (pin "14") (pinfunction "~{RST}_14") (pintype "passive"))
    )
    (net (code "200") (name "Net-(U7-5V)") (class "Default")
      (node (ref "C44") (pin "2") (pinfunction "2_2") (pintype "passive"))
      (node (ref "U7") (pin "18") (pinfunction "5V_18") (pintype "passive"))
    )
    (net (code "201") (name "Net-(U7-BO)") (class "Default")
      (node (ref "P14") (pin "1") (pinfunction "1_1") (pintype "passive"))
      (node (ref "U7") (pin "20") (pinfunction "BO_20") (pintype "passive"))
    )
    (net (code "202") (name "Net-(U7-Rdelay)") (class "Default")
      (node (ref "C48") (pin "2") (pinfunction "2_2") (pintype "passive"))
      (node (ref "U7") (pin "13") (pinfunction "Rdelay_13") (pintype "passive"))
    )
    (net (code "203") (name "Net-(U7-Vin)") (class "Default")
      (node (ref "C40") (pin "2") (pinfunction "2_2") (pintype "passive"))
      (node (ref "R151") (pin "1") (pinfunction "1_1") (pintype "passive"))
      (node (ref "U7") (pin "19") (pinfunction "Vin_19") (pintype "passive"))
    )
    (net (code "204") (name "Net-(U7-~{RST})") (class "Default")
      (node (ref "P18") (pin "1") (pinfunction "1_1") (pintype "passive"))
      (node (ref "U7") (pin "14") (pinfunction "~{RST}_14") (pintype "passive"))
    )
    (net (code "205") (name "Net-(U8-5V)") (class "Default")
      (node (ref "C45") (pin "2") (pinfunction "2_2") (pintype "passive"))
      (node (ref "U8") (pin "18") (pinfunction "5V_18") (pintype "passive"))
    )
    (net (code "206") (name "Net-(U8-BO)") (class "Default")
      (node (ref "P15") (pin "1") (pinfunction "1_1") (pintype "passive"))
      (node (ref "U8") (pin "20") (pinfunction "BO_20") (pintype "passive"))
    )
    (net (code "207") (name "Net-(U8-Rdelay)") (class "Default")
      (node (ref "C49") (pin "2") (pinfunction "2_2") (pintype "passive"))
      (node (ref "U8") (pin "13") (pinfunction "Rdelay_13") (pintype "passive"))
    )
    (net (code "208") (name "Net-(U8-Vin)") (class "Default")
      (node (ref "C41") (pin "2") (pinfunction "2_2") (pintype "passive"))
      (node (ref "R152") (pin "1") (pinfunction "1_1") (pintype "passive"))
      (node (ref "U8") (pin "19") (pinfunction "Vin_19") (pintype "passive"))
    )
    (net (code "209") (name "Net-(U8-~{RST})") (class "Default")
      (node (ref "P19") (pin "1") (pinfunction "1_1") (pintype "passive"))
      (node (ref "U8") (pin "14") (pinfunction "~{RST}_14") (pintype "passive"))
    )
    (net (code "210") (name "Net-(U9-5V)") (class "Default")
      (node (ref "C54") (pin "2") (pinfunction "2_2") (pintype "passive"))
      (node (ref "U9") (pin "18") (pinfunction "5V_18") (pintype "passive"))
    )
    (net (code "211") (name "Net-(U9-BO)") (class "Default")
      (node (ref "P20") (pin "1") (pinfunction "1_1") (pintype "passive"))
      (node (ref "U9") (pin "20") (pinfunction "BO_20") (pintype "passive"))
    )
    (net (code "212") (name "Net-(U9-Rdelay)") (class "Default")
      (node (ref "C58") (pin "2") (pinfunction "2_2") (pintype "passive"))
      (node (ref "U9") (pin "13") (pinfunction "Rdelay_13") (pintype "passive"))
    )
    (net (code "213") (name "Net-(U9-Vin)") (class "Default")
      (node (ref "C50") (pin "2") (pinfunction "2_2") (pintype "passive"))
      (node (ref "R153") (pin "1") (pinfunction "1_1") (pintype "passive"))
      (node (ref "U9") (pin "19") (pinfunction "Vin_19") (pintype "passive"))
    )
    (net (code "214") (name "Net-(U9-~{RST})") (class "Default")
      (node (ref "P24") (pin "1") (pinfunction "1_1") (pintype "passive"))
      (node (ref "U9") (pin "14") (pinfunction "~{RST}_14") (pintype "passive"))
    )
    (net (code "215") (name "Net-(U12-5V)") (class "Default")
      (node (ref "C55") (pin "2") (pinfunction "2_2") (pintype "passive"))
      (node (ref "U12") (pin "18") (pinfunction "5V_18") (pintype "passive"))
    )
    (net (code "216") (name "Net-(U12-BO)") (class "Default")
      (node (ref "P21") (pin "1") (pinfunction "1_1") (pintype "passive"))
      (node (ref "U12") (pin "20") (pinfunction "BO_20") (pintype "passive"))
    )
    (net (code "217") (name "Net-(U12-Rdelay)") (class "Default")
      (node (ref "C59") (pin "2") (pinfunction "2_2") (pintype "passive"))
      (node (ref "U12") (pin "13") (pinfunction "Rdelay_13") (pintype "passive"))
    )
    (net (code "218") (name "Net-(U12-Vin)") (class "Default")
      (node (ref "C51") (pin "2") (pinfunction "2_2") (pintype "passive"))
      (node (ref "R154") (pin "1") (pinfunction "1_1") (pintype "passive"))
      (node (ref "U12") (pin "19") (pinfunction "Vin_19") (pintype "passive"))
    )
    (net (code "219") (name "Net-(U12-~{RST})") (class "Default")
      (node (ref "P25") (pin "1") (pinfunction "1_1") (pintype "passive"))
      (node (ref "U12") (pin "14") (pinfunction "~{RST}_14") (pintype "passive"))
    )
    (net (code "220") (name "Net-(U14-5V)") (class "Default")
      (node (ref "C56") (pin "2") (pinfunction "2_2") (pintype "passive"))
      (node (ref "U14") (pin "18") (pinfunction "5V_18") (pintype "passive"))
    )
    (net (code "221") (name "Net-(U14-BO)") (class "Default")
      (node (ref "P22") (pin "1") (pinfunction "1_1") (pintype "passive"))
      (node (ref "U14") (pin "20") (pinfunction "BO_20") (pintype "passive"))
    )
    (net (code "222") (name "Net-(U14-Rdelay)") (class "Default")
      (node (ref "C60") (pin "2") (pinfunction "2_2") (pintype "passive"))
      (node (ref "U14") (pin "13") (pinfunction "Rdelay_13") (pintype "passive"))
    )
    (net (code "223") (name "Net-(U14-Vin)") (class "Default")
      (node (ref "C52") (pin "2") (pinfunction "2_2") (pintype "passive"))
      (node (ref "R155") (pin "1") (pinfunction "1_1") (pintype "passive"))
      (node (ref "U14") (pin "19") (pinfunction "Vin_19") (pintype "passive"))
    )
    (net (code "224") (name "Net-(U14-~{RST})") (class "Default")
      (node (ref "P26") (pin "1") (pinfunction "1_1") (pintype "passive"))
      (node (ref "U14") (pin "14") (pinfunction "~{RST}_14") (pintype "passive"))
    )
    (net (code "225") (name "Net-(U15-5V)") (class "Default")
      (node (ref "C57") (pin "2") (pinfunction "2_2") (pintype "passive"))
      (node (ref "U15") (pin "18") (pinfunction "5V_18") (pintype "passive"))
    )
    (net (code "226") (name "Net-(U15-BO)") (class "Default")
      (node (ref "P23") (pin "1") (pinfunction "1_1") (pintype "passive"))
      (node (ref "U15") (pin "20") (pinfunction "BO_20") (pintype "passive"))
    )
    (net (code "227") (name "Net-(U15-Rdelay)") (class "Default")
      (node (ref "C61") (pin "2") (pinfunction "2_2") (pintype "passive"))
      (node (ref "U15") (pin "13") (pinfunction "Rdelay_13") (pintype "passive"))
    )
    (net (code "228") (name "Net-(U15-Vin)") (class "Default")
      (node (ref "C53") (pin "2") (pinfunction "2_2") (pintype "passive"))
      (node (ref "R156") (pin "1") (pinfunction "1_1") (pintype "passive"))
      (node (ref "U15") (pin "19") (pinfunction "Vin_19") (pintype "passive"))
    )
    (net (code "229") (name "Net-(U15-~{RST})") (class "Default")
      (node (ref "P27") (pin "1") (pinfunction "1_1") (pintype "passive"))
      (node (ref "U15") (pin "14") (pinfunction "~{RST}_14") (pintype "passive"))
    )
    (net (code "230") (name "Net-(U16-5V)") (class "Default")
      (node (ref "C66") (pin "2") (pinfunction "2_2") (pintype "passive"))
      (node (ref "U16") (pin "18") (pinfunction "5V_18") (pintype "passive"))
    )
    (net (code "231") (name "Net-(U16-BO)") (class "Default")
      (node (ref "P28") (pin "1") (pinfunction "1_1") (pintype "passive"))
      (node (ref "U16") (pin "20") (pinfunction "BO_20") (pintype "passive"))
    )
    (net (code "232") (name "Net-(U16-Rdelay)") (class "Default")
      (node (ref "C70") (pin "2") (pinfunction "2_2") (pintype "passive"))
      (node (ref "U16") (pin "13") (pinfunction "Rdelay_13") (pintype "passive"))
    )
    (net (code "233") (name "Net-(U16-Vin)") (class "Default")
      (node (ref "C62") (pin "2") (pinfunction "2_2") (pintype "passive"))
      (node (ref "R157") (pin "1") (pinfunction "1_1") (pintype "passive"))
      (node (ref "U16") (pin "19") (pinfunction "Vin_19") (pintype "passive"))
    )
    (net (code "234") (name "Net-(U16-~{RST})") (class "Default")
      (node (ref "P32") (pin "1") (pinfunction "1_1") (pintype "passive"))
      (node (ref "U16") (pin "14") (pinfunction "~{RST}_14") (pintype "passive"))
    )
    (net (code "235") (name "Net-(U17-5V)") (class "Default")
      (node (ref "C67") (pin "2") (pinfunction "2_2") (pintype "passive"))
      (node (ref "U17") (pin "18") (pinfunction "5V_18") (pintype "passive"))
    )
    (net (code "236") (name "Net-(U17-BO)") (class "Default")
      (node (ref "P29") (pin "1") (pinfunction "1_1") (pintype "passive"))
      (node (ref "U17") (pin "20") (pinfunction "BO_20") (pintype "passive"))
    )
    (net (code "237") (name "Net-(U17-Rdelay)") (class "Default")
      (node (ref "C71") (pin "2") (pinfunction "2_2") (pintype "passive"))
      (node (ref "U17") (pin "13") (pinfunction "Rdelay_13") (pintype "passive"))
    )
    (net (code "238") (name "Net-(U17-Vin)") (class "Default")
      (node (ref "C63") (pin "2") (pinfunction "2_2") (pintype "passive"))
      (node (ref "R158") (pin "1") (pinfunction "1_1") (pintype "passive"))
      (node (ref "U17") (pin "19") (pinfunction "Vin_19") (pintype "passive"))
    )
    (net (code "239") (name "Net-(U17-~{RST})") (class "Default")
      (node (ref "P33") (pin "1") (pinfunction "1_1") (pintype "passive"))
      (node (ref "U17") (pin "14") (pinfunction "~{RST}_14") (pintype "passive"))
    )
    (net (code "240") (name "Net-(U18-5V)") (class "Default")
      (node (ref "C68") (pin "2") (pinfunction "2_2") (pintype "passive"))
      (node (ref "U18") (pin "18") (pinfunction "5V_18") (pintype "passive"))
    )
    (net (code "241") (name "Net-(U18-BO)") (class "Default")
      (node (ref "P30") (pin "1") (pinfunction "1_1") (pintype "passive"))
      (node (ref "U18") (pin "20") (pinfunction "BO_20") (pintype "passive"))
    )
    (net (code "242") (name "Net-(U18-Rdelay)") (class "Default")
      (node (ref "C72") (pin "2") (pinfunction "2_2") (pintype "passive"))
      (node (ref "U18") (pin "13") (pinfunction "Rdelay_13") (pintype "passive"))
    )
    (net (code "243") (name "Net-(U18-Vin)") (class "Default")
      (node (ref "C64") (pin "2") (pinfunction "2_2") (pintype "passive"))
      (node (ref "R159") (pin "1") (pinfunction "1_1") (pintype "passive"))
      (node (ref "U18") (pin "19") (pinfunction "Vin_19") (pintype "passive"))
    )
    (net (code "244") (name "Net-(U18-~{RST})") (class "Default")
      (node (ref "P34") (pin "1") (pinfunction "1_1") (pintype "passive"))
      (node (ref "U18") (pin "14") (pinfunction "~{RST}_14") (pintype "passive"))
    )
    (net (code "245") (name "Net-(U19-5V)") (class "Default")
      (node (ref "C69") (pin "2") (pinfunction "2_2") (pintype "passive"))
      (node (ref "U19") (pin "18") (pinfunction "5V_18") (pintype "passive"))
    )
    (net (code "246") (name "Net-(U19-BO)") (class "Default")
      (node (ref "P31") (pin "1") (pinfunction "1_1") (pintype "passive"))
      (node (ref "U19") (pin "20") (pinfunction "BO_20") (pintype "passive"))
    )
    (net (code "247") (name "Net-(U19-Rdelay)") (class "Default")
      (node (ref "C73") (pin "2") (pinfunction "2_2") (pintype "passive"))
      (node (ref "U19") (pin "13") (pinfunction "Rdelay_13") (pintype "passive"))
    )
    (net (code "248") (name "Net-(U19-Vin)") (class "Default")
      (node (ref "C65") (pin "2") (pinfunction "2_2") (pintype "passive"))
      (node (ref "R160") (pin "1") (pinfunction "1_1") (pintype "passive"))
      (node (ref "U19") (pin "19") (pinfunction "Vin_19") (pintype "passive"))
    )
    (net (code "249") (name "Net-(U19-~{RST})") (class "Default")
      (node (ref "P35") (pin "1") (pinfunction "1_1") (pintype "passive"))
      (node (ref "U19") (pin "14") (pinfunction "~{RST}_14") (pintype "passive"))
    )
    (net (code "250") (name "Net-(U20-5V)") (class "Default")
      (node (ref "C76") (pin "2") (pinfunction "2_2") (pintype "passive"))
      (node (ref "U20") (pin "18") (pinfunction "5V_18") (pintype "passive"))
    )
    (net (code "251") (name "Net-(U20-BO)") (class "Default")
      (node (ref "P36") (pin "1") (pinfunction "1_1") (pintype "passive"))
      (node (ref "U20") (pin "20") (pinfunction "BO_20") (pintype "passive"))
    )
    (net (code "252") (name "Net-(U20-Rdelay)") (class "Default")
      (node (ref "C78") (pin "2") (pinfunction "2_2") (pintype "passive"))
      (node (ref "U20") (pin "13") (pinfunction "Rdelay_13") (pintype "passive"))
    )
    (net (code "253") (name "Net-(U20-Vin)") (class "Default")
      (node (ref "C74") (pin "2") (pinfunction "2_2") (pintype "passive"))
      (node (ref "R161") (pin "1") (pinfunction "1_1") (pintype "passive"))
      (node (ref "U20") (pin "19") (pinfunction "Vin_19") (pintype "passive"))
    )
    (net (code "254") (name "Net-(U20-~{RST})") (class "Default")
      (node (ref "P39") (pin "1") (pinfunction "1_1") (pintype "passive"))
      (node (ref "U20") (pin "14") (pinfunction "~{RST}_14") (pintype "passive"))
    )
    (net (code "255") (name "Net-(U21-BO)") (class "Default")
      (node (ref "P37") (pin "1") (pinfunction "1_1") (pintype "passive"))
      (node (ref "U21") (pin "20") (pinfunction "BO_20") (pintype "passive"))
    )
    (net (code "256") (name "Net-(U21-Rdelay)") (class "Default")
      (node (ref "C79") (pin "2") (pinfunction "2_2") (pintype "passive"))
      (node (ref "U21") (pin "13") (pinfunction "Rdelay_13") (pintype "passive"))
    )
    (net (code "257") (name "Net-(U21-Vin)") (class "Default")
      (node (ref "C75") (pin "2") (pinfunction "2_2") (pintype "passive"))
      (node (ref "R162") (pin "1") (pinfunction "1_1") (pintype "passive"))
      (node (ref "U21") (pin "19") (pinfunction "Vin_19") (pintype "passive"))
    )
    (net (code "258") (name "Net-(U21-~{RST})") (class "Default")
      (node (ref "P40") (pin "1") (pinfunction "1_1") (pintype "passive"))
      (node (ref "U21") (pin "14") (pinfunction "~{RST}_14") (pintype "passive"))
    )
    (net (code "259") (name "unconnected-(U1-BO_OUTZ-Pad1)") (class "Default")
      (node (ref "U1") (pin "1") (pinfunction "BO_OUTZ_1") (pintype "passive"))
    )
    (net (code "260") (name "unconnected-(U1-NC-Pad11)") (class "Default")
      (node (ref "U1") (pin "11") (pinfunction "NC_11") (pintype "passive"))
    )
    (net (code "261") (name "unconnected-(U2-BO_OUTZ-Pad1)") (class "Default")
      (node (ref "U2") (pin "1") (pinfunction "BO_OUTZ_1") (pintype "passive"))
    )
    (net (code "262") (name "unconnected-(U2-NC-Pad11)") (class "Default")
      (node (ref "U2") (pin "11") (pinfunction "NC_11") (pintype "passive"))
    )
    (net (code "263") (name "unconnected-(U3-BO_OUTZ-Pad1)") (class "Default")
      (node (ref "U3") (pin "1") (pinfunction "BO_OUTZ_1") (pintype "passive"))
    )
    (net (code "264") (name "unconnected-(U3-NC-Pad11)") (class "Default")
      (node (ref "U3") (pin "11") (pinfunction "NC_11") (pintype "passive"))
    )
    (net (code "265") (name "unconnected-(U4-BO_OUTZ-Pad1)") (class "Default")
      (node (ref "U4") (pin "1") (pinfunction "BO_OUTZ_1") (pintype "passive"))
    )
    (net (code "266") (name "unconnected-(U4-NC-Pad11)") (class "Default")
      (node (ref "U4") (pin "11") (pinfunction "NC_11") (pintype "passive"))
    )
    (net (code "267") (name "unconnected-(U5-BO_OUTZ-Pad1)") (class "Default")
      (node (ref "U5") (pin "1") (pinfunction "BO_OUTZ_1") (pintype "passive"))
    )
    (net (code "268") (name "unconnected-(U5-NC-Pad11)") (class "Default")
      (node (ref "U5") (pin "11") (pinfunction "NC_11") (pintype "passive"))
    )
    (net (code "269") (name "unconnected-(U6-BO_OUTZ-Pad1)") (class "Default")
      (node (ref "U6") (pin "1") (pinfunction "BO_OUTZ_1") (pintype "passive"))
    )
    (net (code "270") (name "unconnected-(U6-NC-Pad11)") (class "Default")
      (node (ref "U6") (pin "11") (pinfunction "NC_11") (pintype "passive"))
    )
    (net (code "271") (name "unconnected-(U7-BO_OUTZ-Pad1)") (class "Default")
      (node (ref "U7") (pin "1") (pinfunction "BO_OUTZ_1") (pintype "passive"))
    )
    (net (code "272") (name "unconnected-(U7-NC-Pad11)") (class "Default")
      (node (ref "U7") (pin "11") (pinfunction "NC_11") (pintype "passive"))
    )
    (net (code "273") (name "unconnected-(U8-BO_OUTZ-Pad1)") (class "Default")
      (node (ref "U8") (pin "1") (pinfunction "BO_OUTZ_1") (pintype "passive"))
    )
    (net (code "274") (name "unconnected-(U8-NC-Pad11)") (class "Default")
      (node (ref "U8") (pin "11") (pinfunction "NC_11") (pintype "passive"))
    )
    (net (code "275") (name "unconnected-(U9-BO_OUTZ-Pad1)") (class "Default")
      (node (ref "U9") (pin "1") (pinfunction "BO_OUTZ_1") (pintype "passive"))
    )
    (net (code "276") (name "unconnected-(U9-NC-Pad11)") (class "Default")
      (node (ref "U9") (pin "11") (pinfunction "NC_11") (pintype "passive"))
    )
    (net (code "277") (name "unconnected-(U12-BO_OUTZ-Pad1)") (class "Default")
      (node (ref "U12") (pin "1") (pinfunction "BO_OUTZ_1") (pintype "passive"))
    )
    (net (code "278") (name "unconnected-(U12-NC-Pad11)") (class "Default")
      (node (ref "U12") (pin "11") (pinfunction "NC_11") (pintype "passive"))
    )
    (net (code "279") (name "unconnected-(U14-BO_OUTZ-Pad1)") (class "Default")
      (node (ref "U14") (pin "1") (pinfunction "BO_OUTZ_1") (pintype "passive"))
    )
    (net (code "280") (name "unconnected-(U14-NC-Pad11)") (class "Default")
      (node (ref "U14") (pin "11") (pinfunction "NC_11") (pintype "passive"))
    )
    (net (code "281") (name "unconnected-(U15-BO_OUTZ-Pad1)") (class "Default")
      (node (ref "U15") (pin "1") (pinfunction "BO_OUTZ_1") (pintype "passive"))
    )
    (net (code "282") (name "unconnected-(U15-NC-Pad11)") (class "Default")
      (node (ref "U15") (pin "11") (pinfunction "NC_11") (pintype "passive"))
    )
    (net (code "283") (name "unconnected-(U16-BO_OUTZ-Pad1)") (class "Default")
      (node (ref "U16") (pin "1") (pinfunction "BO_OUTZ_1") (pintype "passive"))
    )
    (net (code "284") (name "unconnected-(U16-NC-Pad11)") (class "Default")
      (node (ref "U16") (pin "11") (pinfunction "NC_11") (pintype "passive"))
    )
    (net (code "285") (name "unconnected-(U17-BO_OUTZ-Pad1)") (class "Default")
      (node (ref "U17") (pin "1") (pinfunction "BO_OUTZ_1") (pintype "passive"))
    )
    (net (code "286") (name "unconnected-(U17-NC-Pad11)") (class "Default")
      (node (ref "U17") (pin "11") (pinfunction "NC_11") (pintype "passive"))
    )
    (net (code "287") (name "unconnected-(U18-BO_OUTZ-Pad1)") (class "Default")
      (node (ref "U18") (pin "1") (pinfunction "BO_OUTZ_1") (pintype "passive"))
    )
    (net (code "288") (name "unconnected-(U18-NC-Pad11)") (class "Default")
      (node (ref "U18") (pin "11") (pinfunction "NC_11") (pintype "passive"))
    )
    (net (code "289") (name "unconnected-(U19-BO_OUTZ-Pad1)") (class "Default")
      (node (ref "U19") (pin "1") (pinfunction "BO_OUTZ_1") (pintype "passive"))
    )
    (net (code "290") (name "unconnected-(U19-NC-Pad11)") (class "Default")
      (node (ref "U19") (pin "11") (pinfunction "NC_11") (pintype "passive"))
    )
    (net (code "291") (name "unconnected-(U20-BO_OUTZ-Pad1)") (class "Default")
      (node (ref "U20") (pin "1") (pinfunction "BO_OUTZ_1") (pintype "passive"))
    )
    (net (code "292") (name "unconnected-(U20-NC-Pad11)") (class "Default")
      (node (ref "U20") (pin "11") (pinfunction "NC_11") (pintype "passive"))
    )
    (net (code "293") (name "unconnected-(U21-BO_OUTZ-Pad1)") (class "Default")
      (node (ref "U21") (pin "1") (pinfunction "BO_OUTZ_1") (pintype "passive"))
    )
    (net (code "294") (name "unconnected-(U21-NC-Pad11)") (class "Default")
      (node (ref "U21") (pin "11") (pinfunction "NC_11") (pintype "passive"))
    )
  )
)
